# PX4FMUlite_V0_3.net
KiCad netlist of a schematic drawn in EAGLE
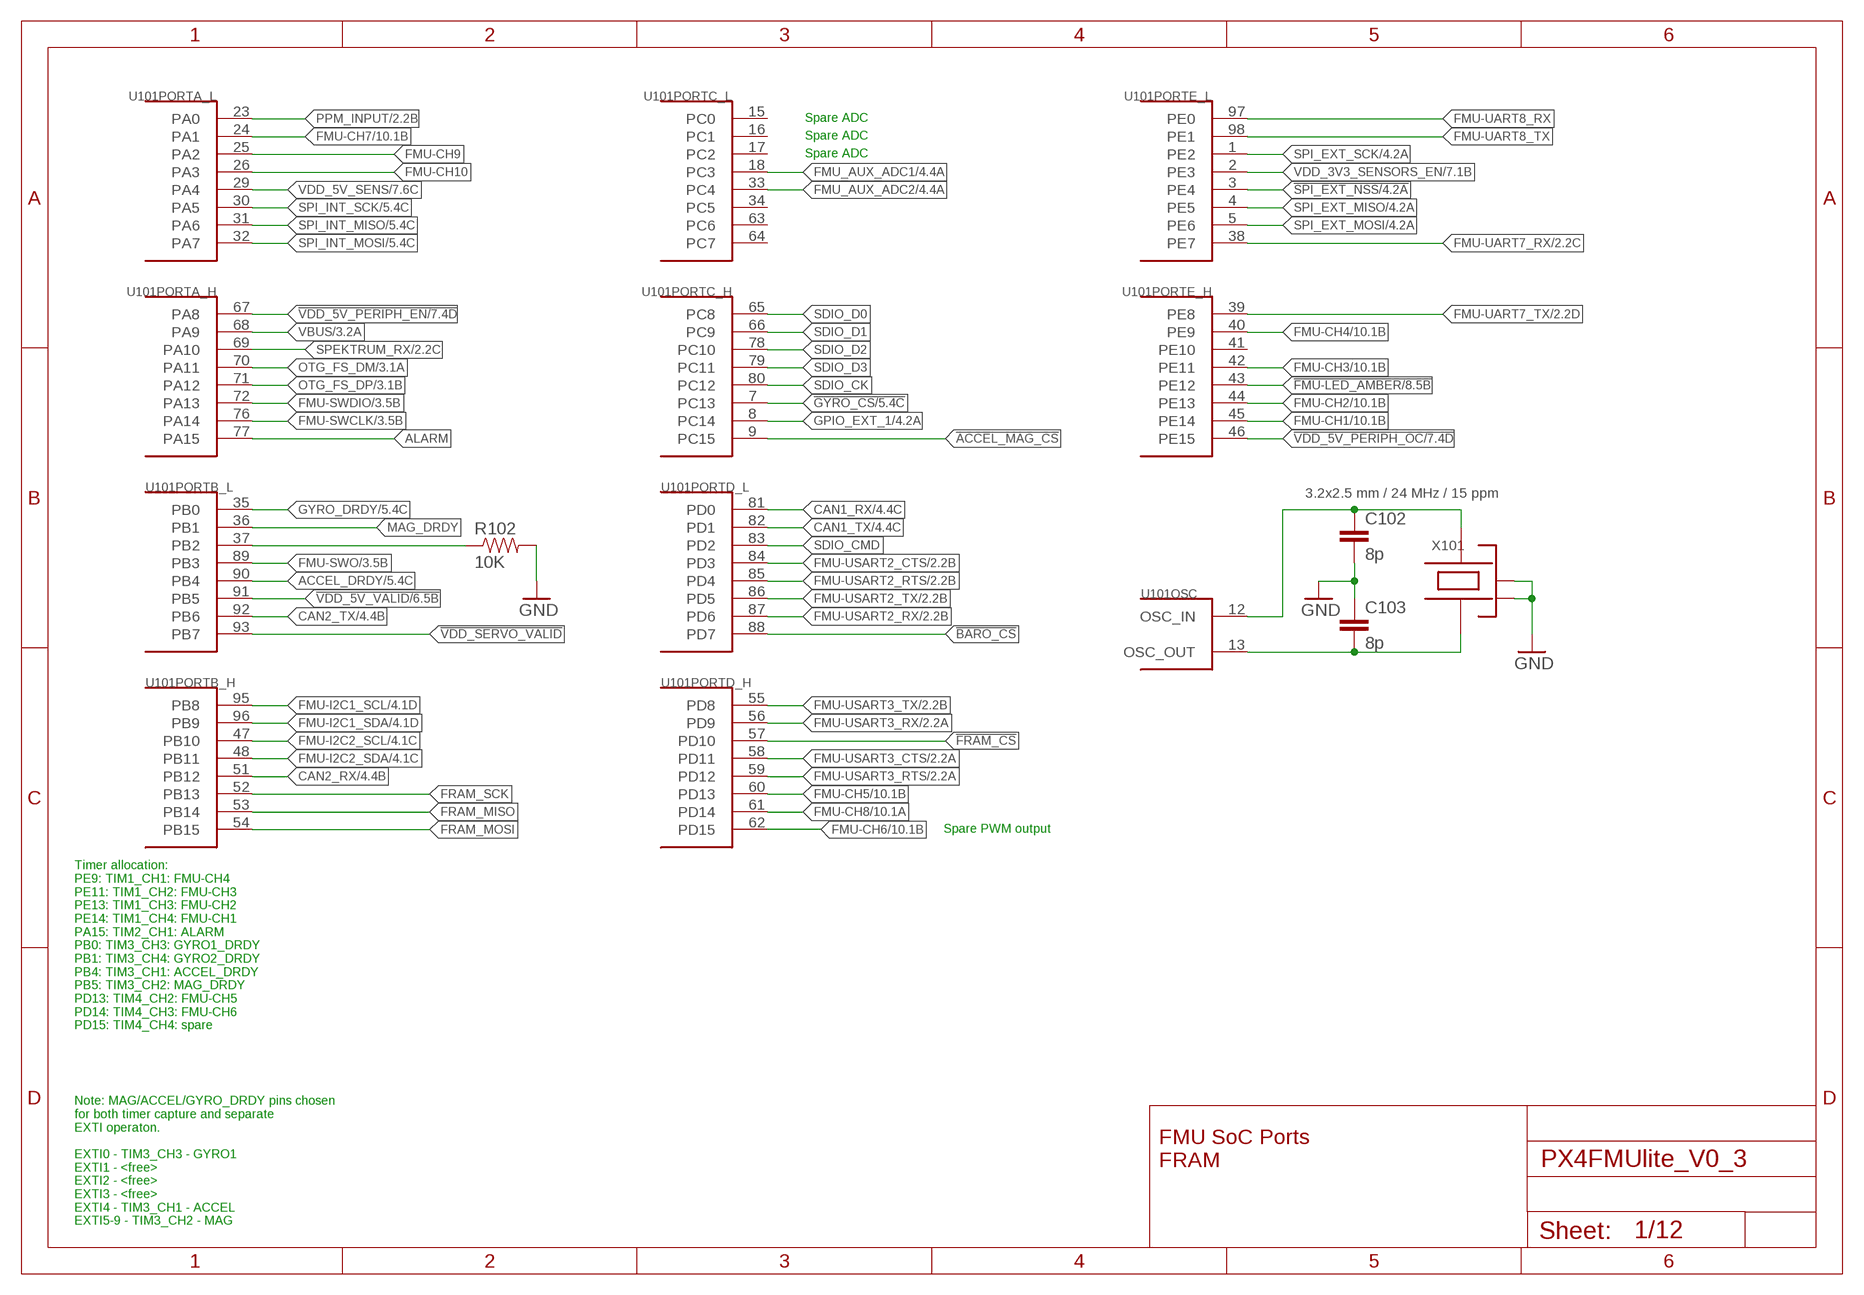
[diagram p0: schematic, sheet 1]
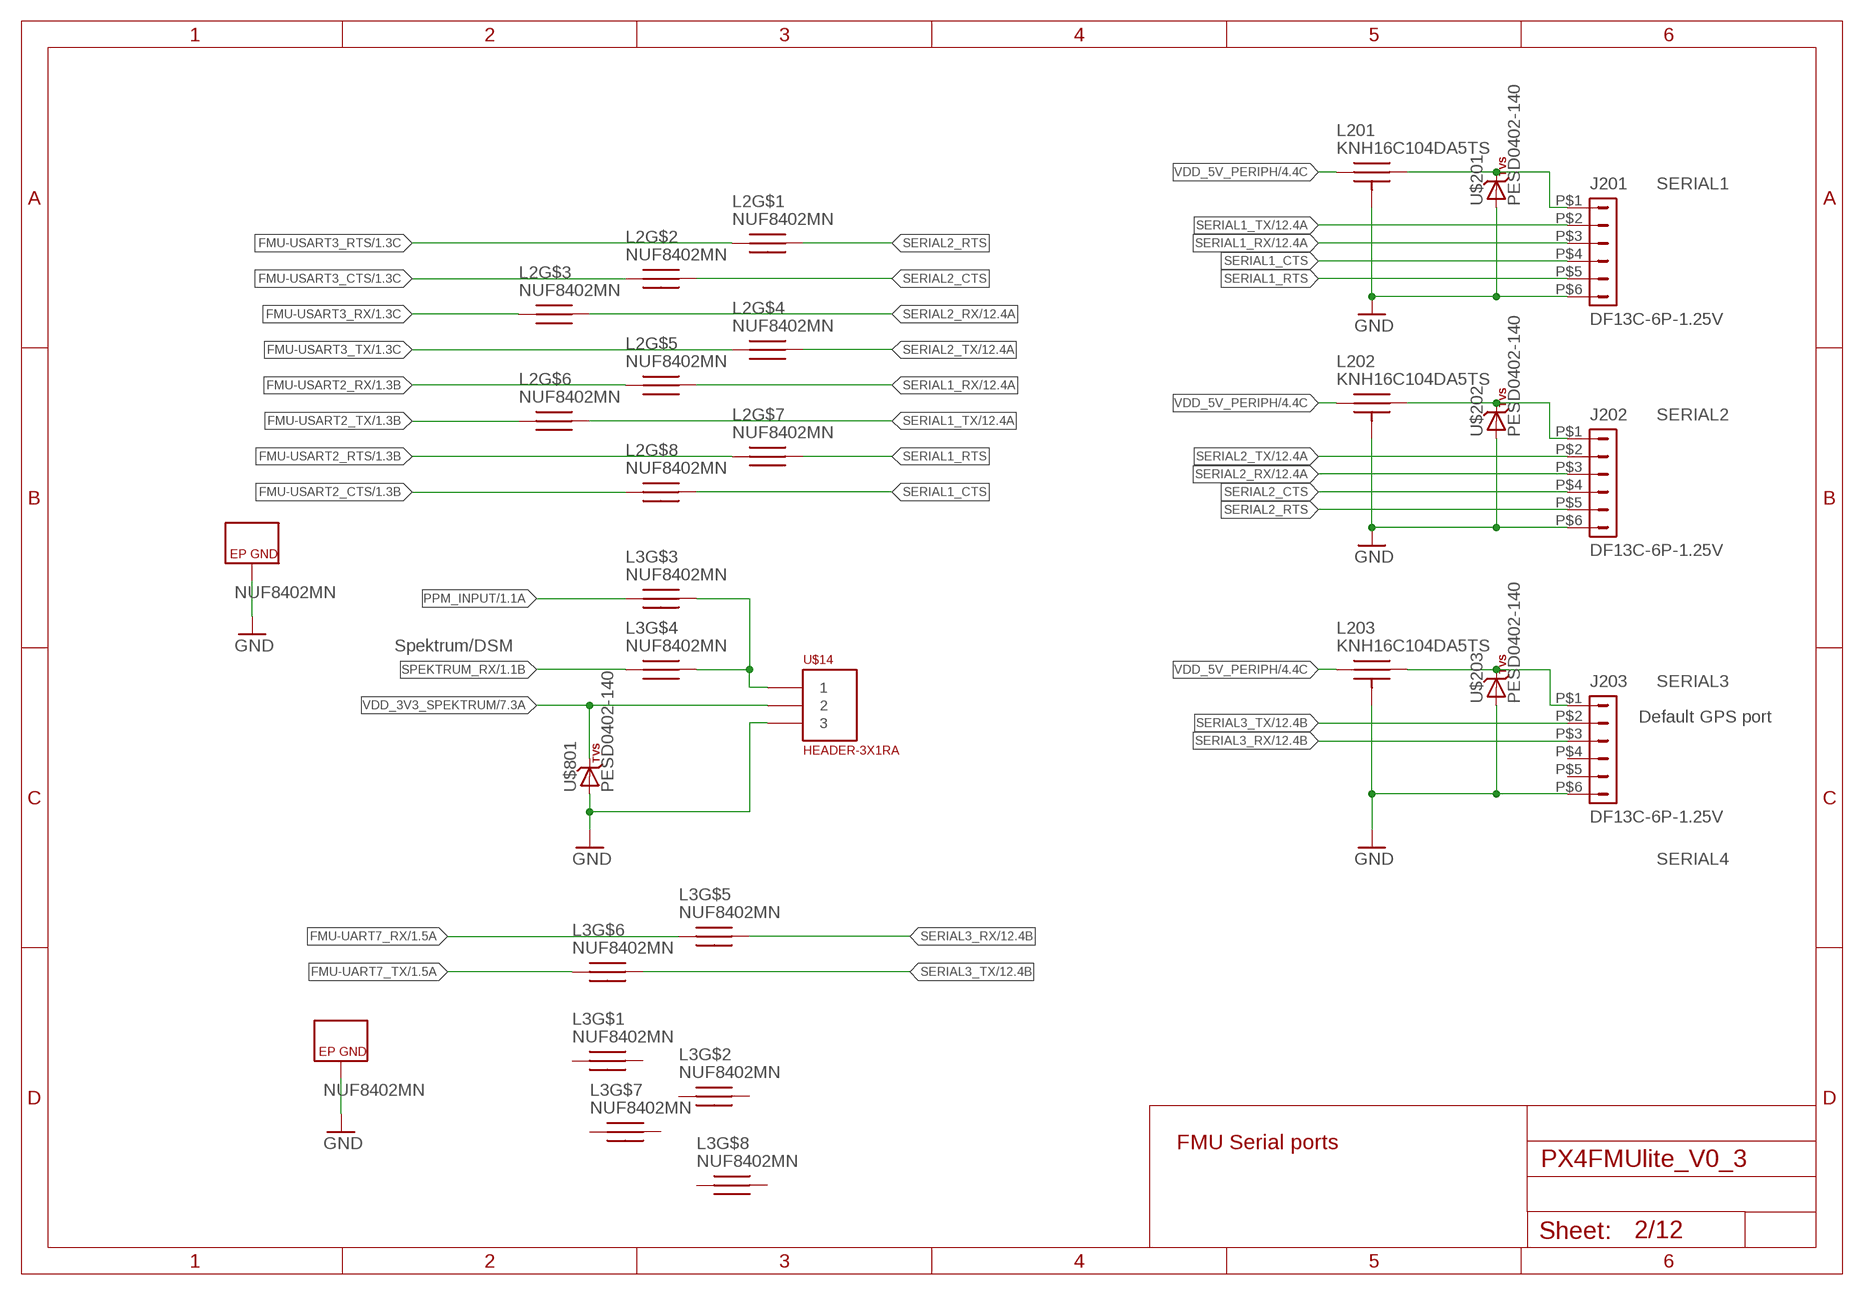
[diagram p1: schematic, sheet 2]
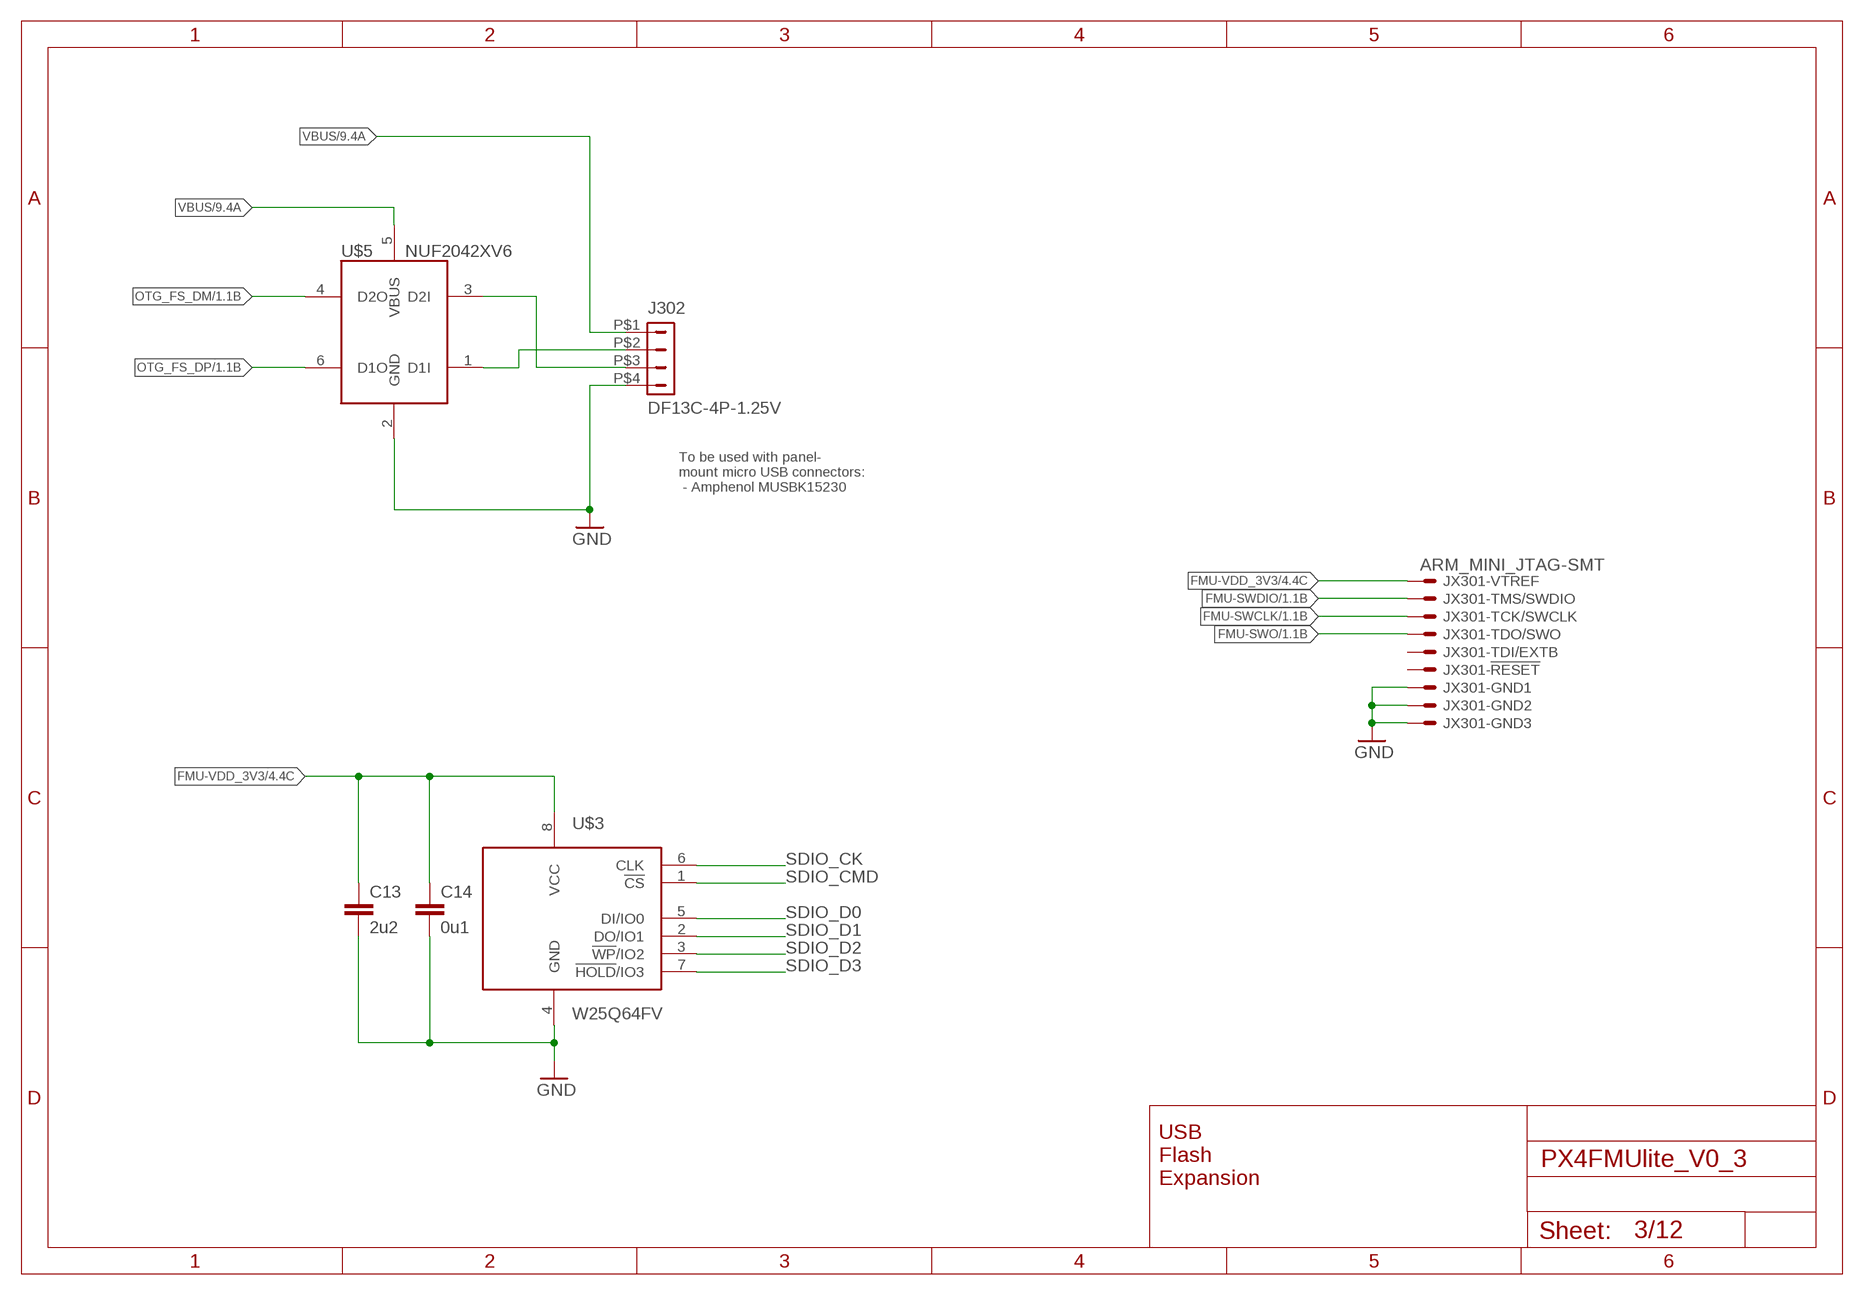
[diagram p2: schematic, sheet 3]
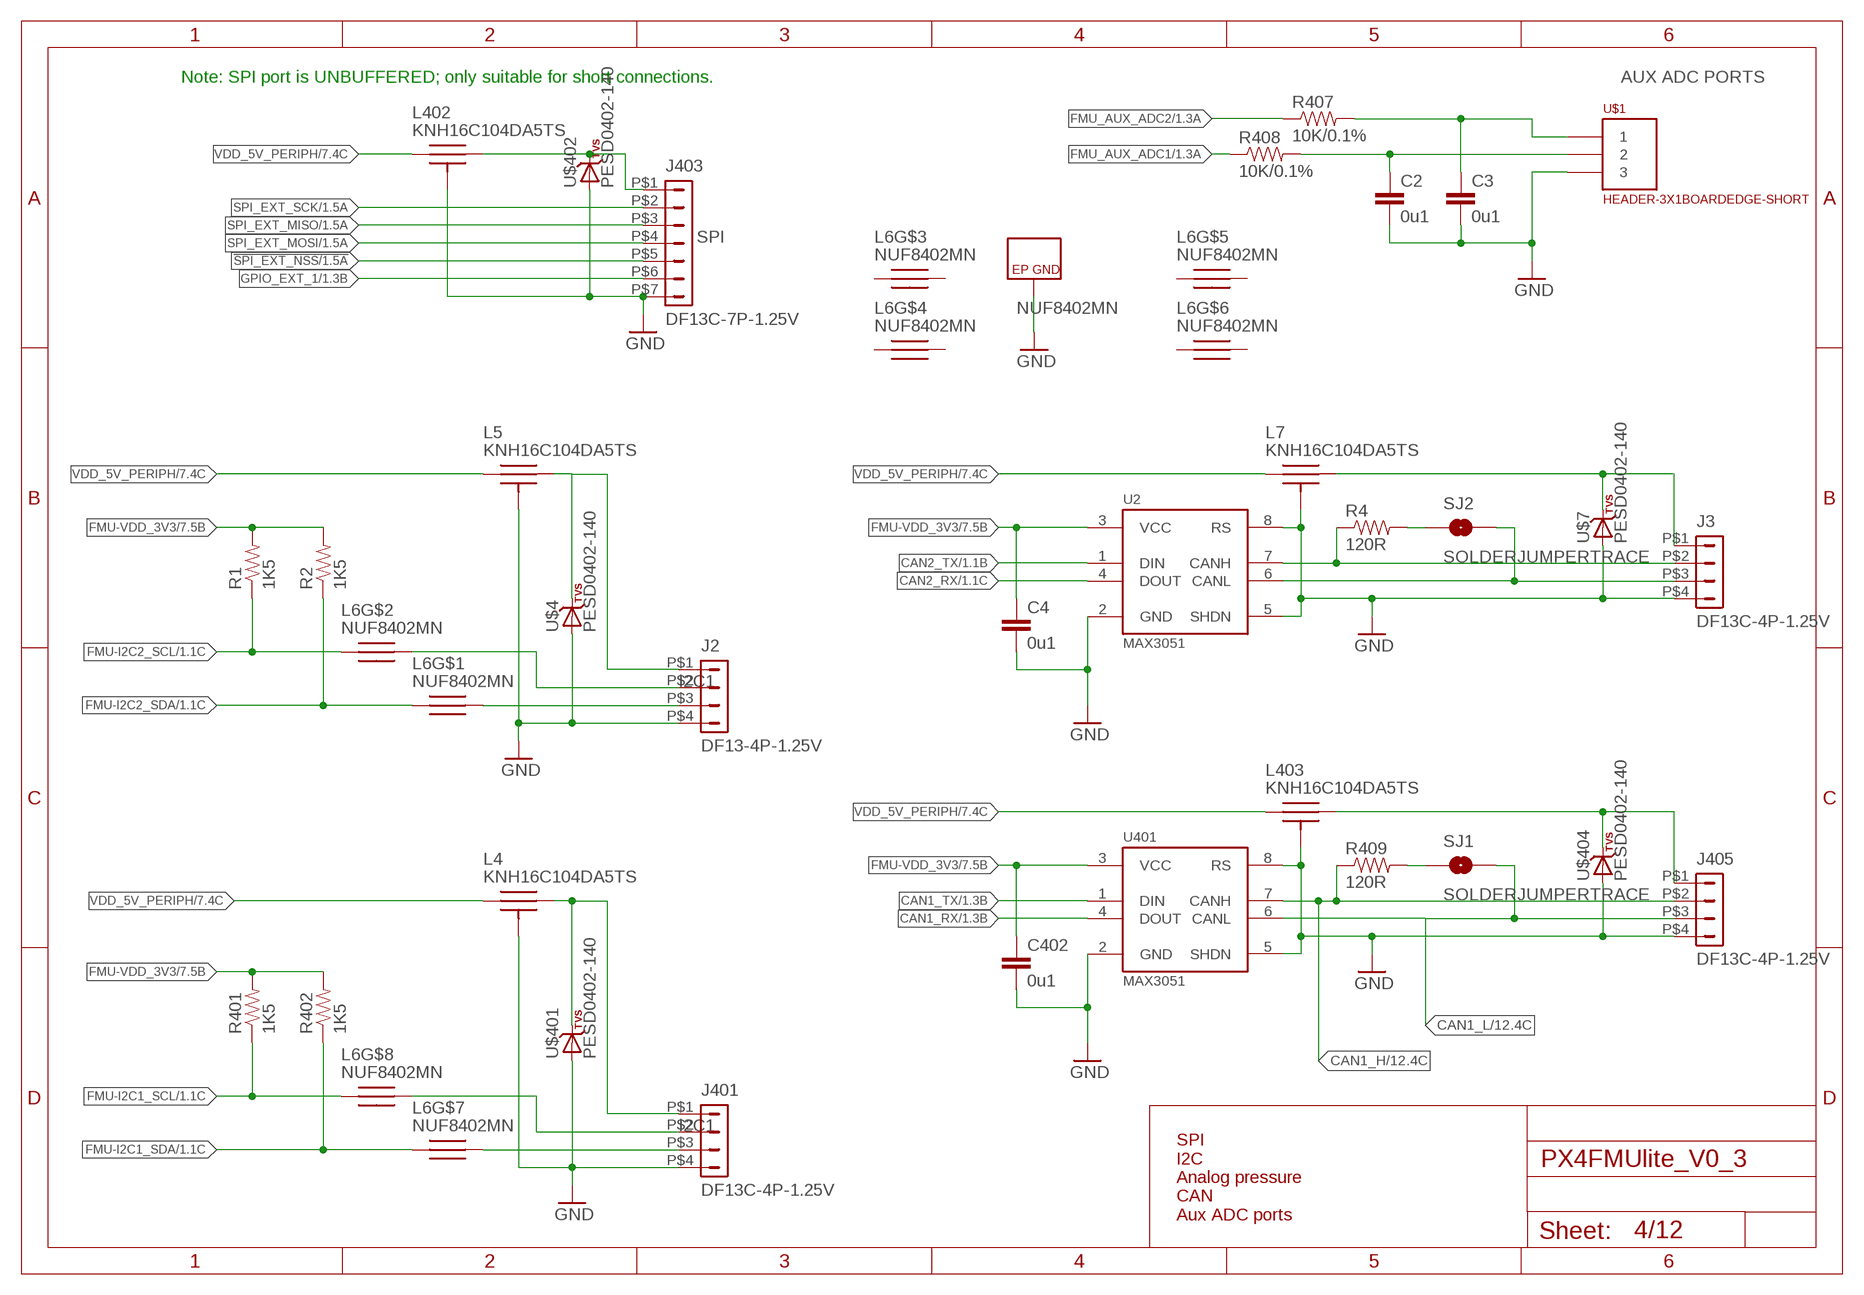
[diagram p3: schematic, sheet 4]
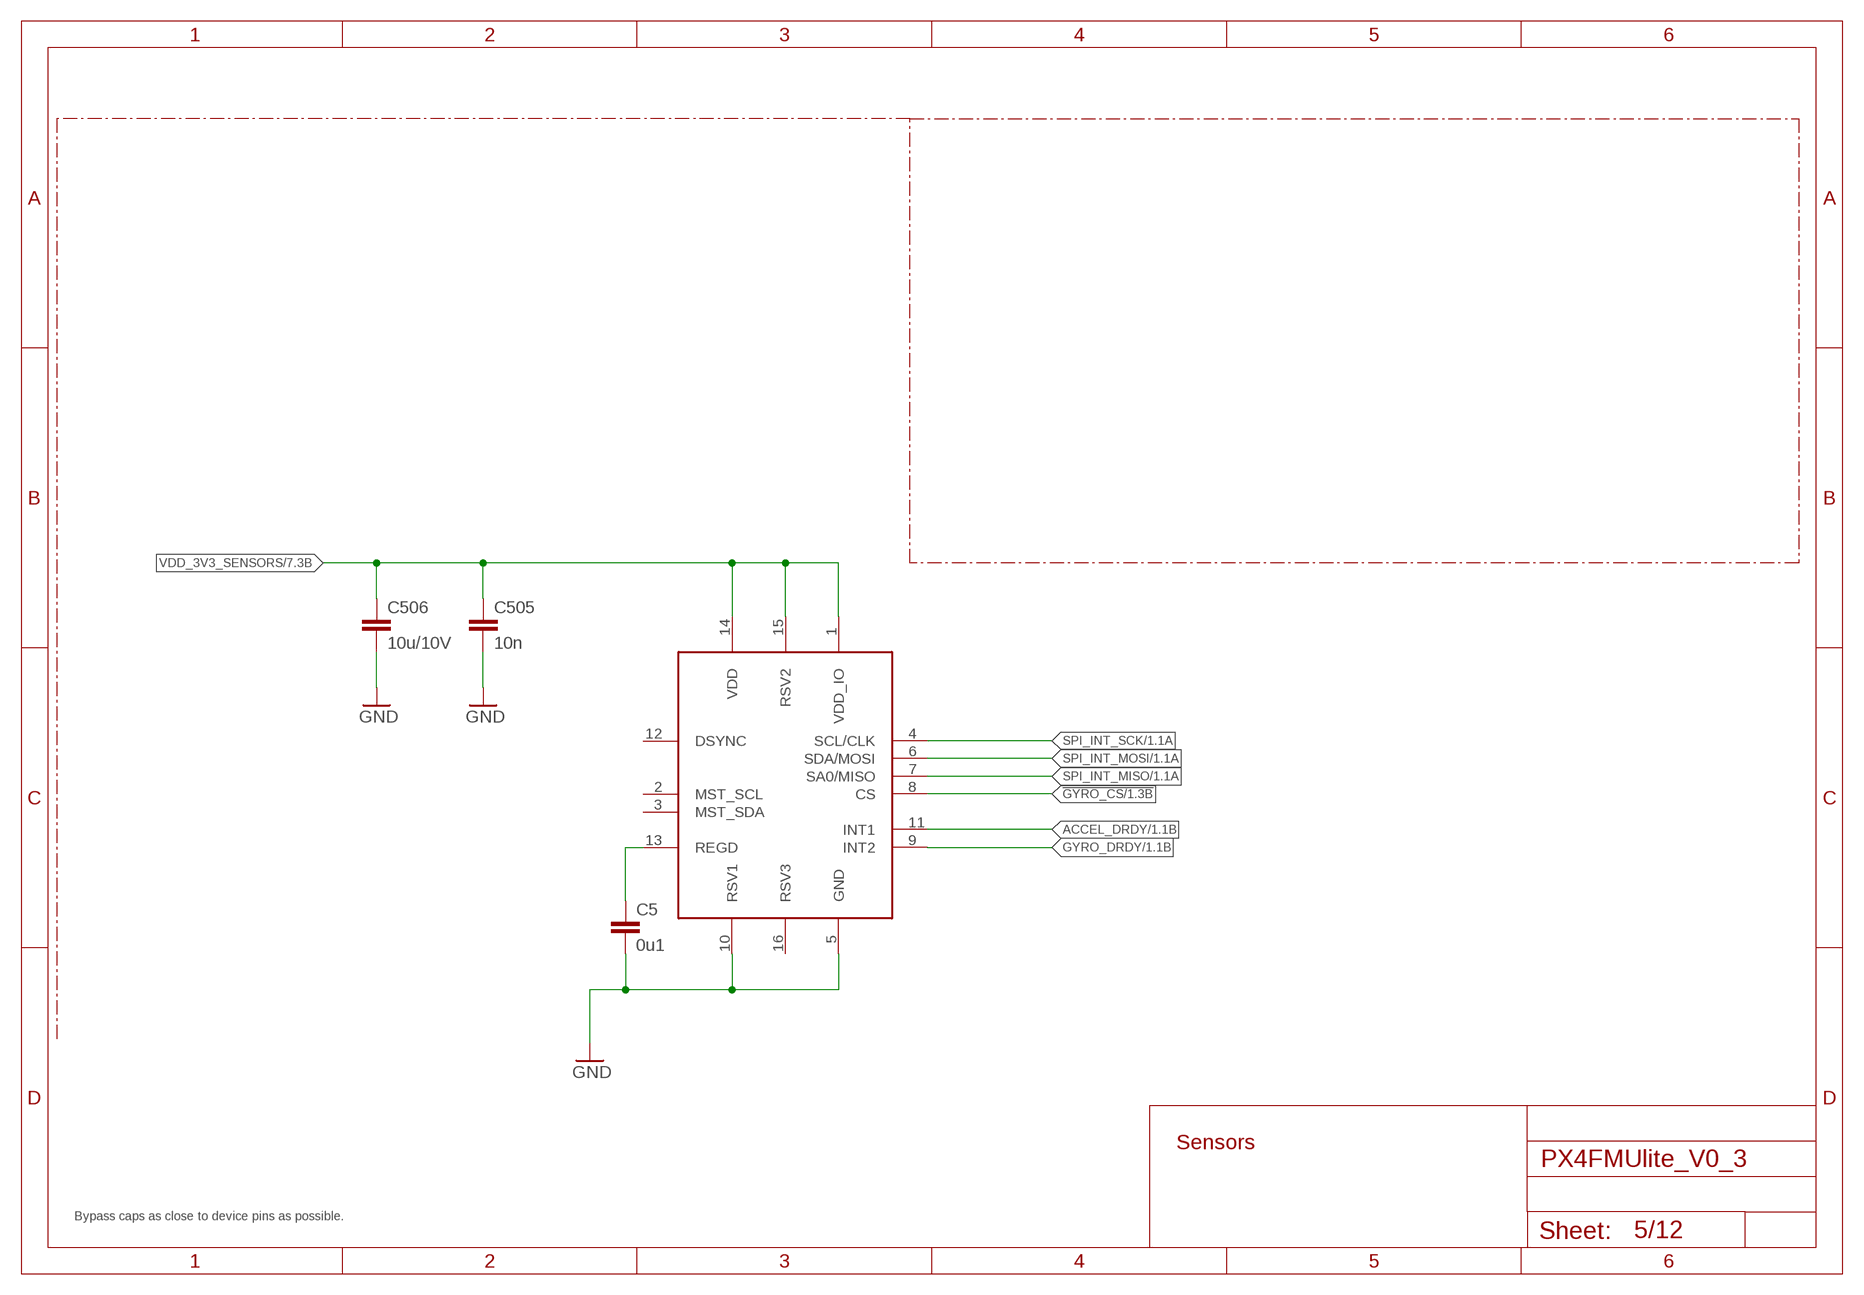
[diagram p4: schematic, sheet 5]
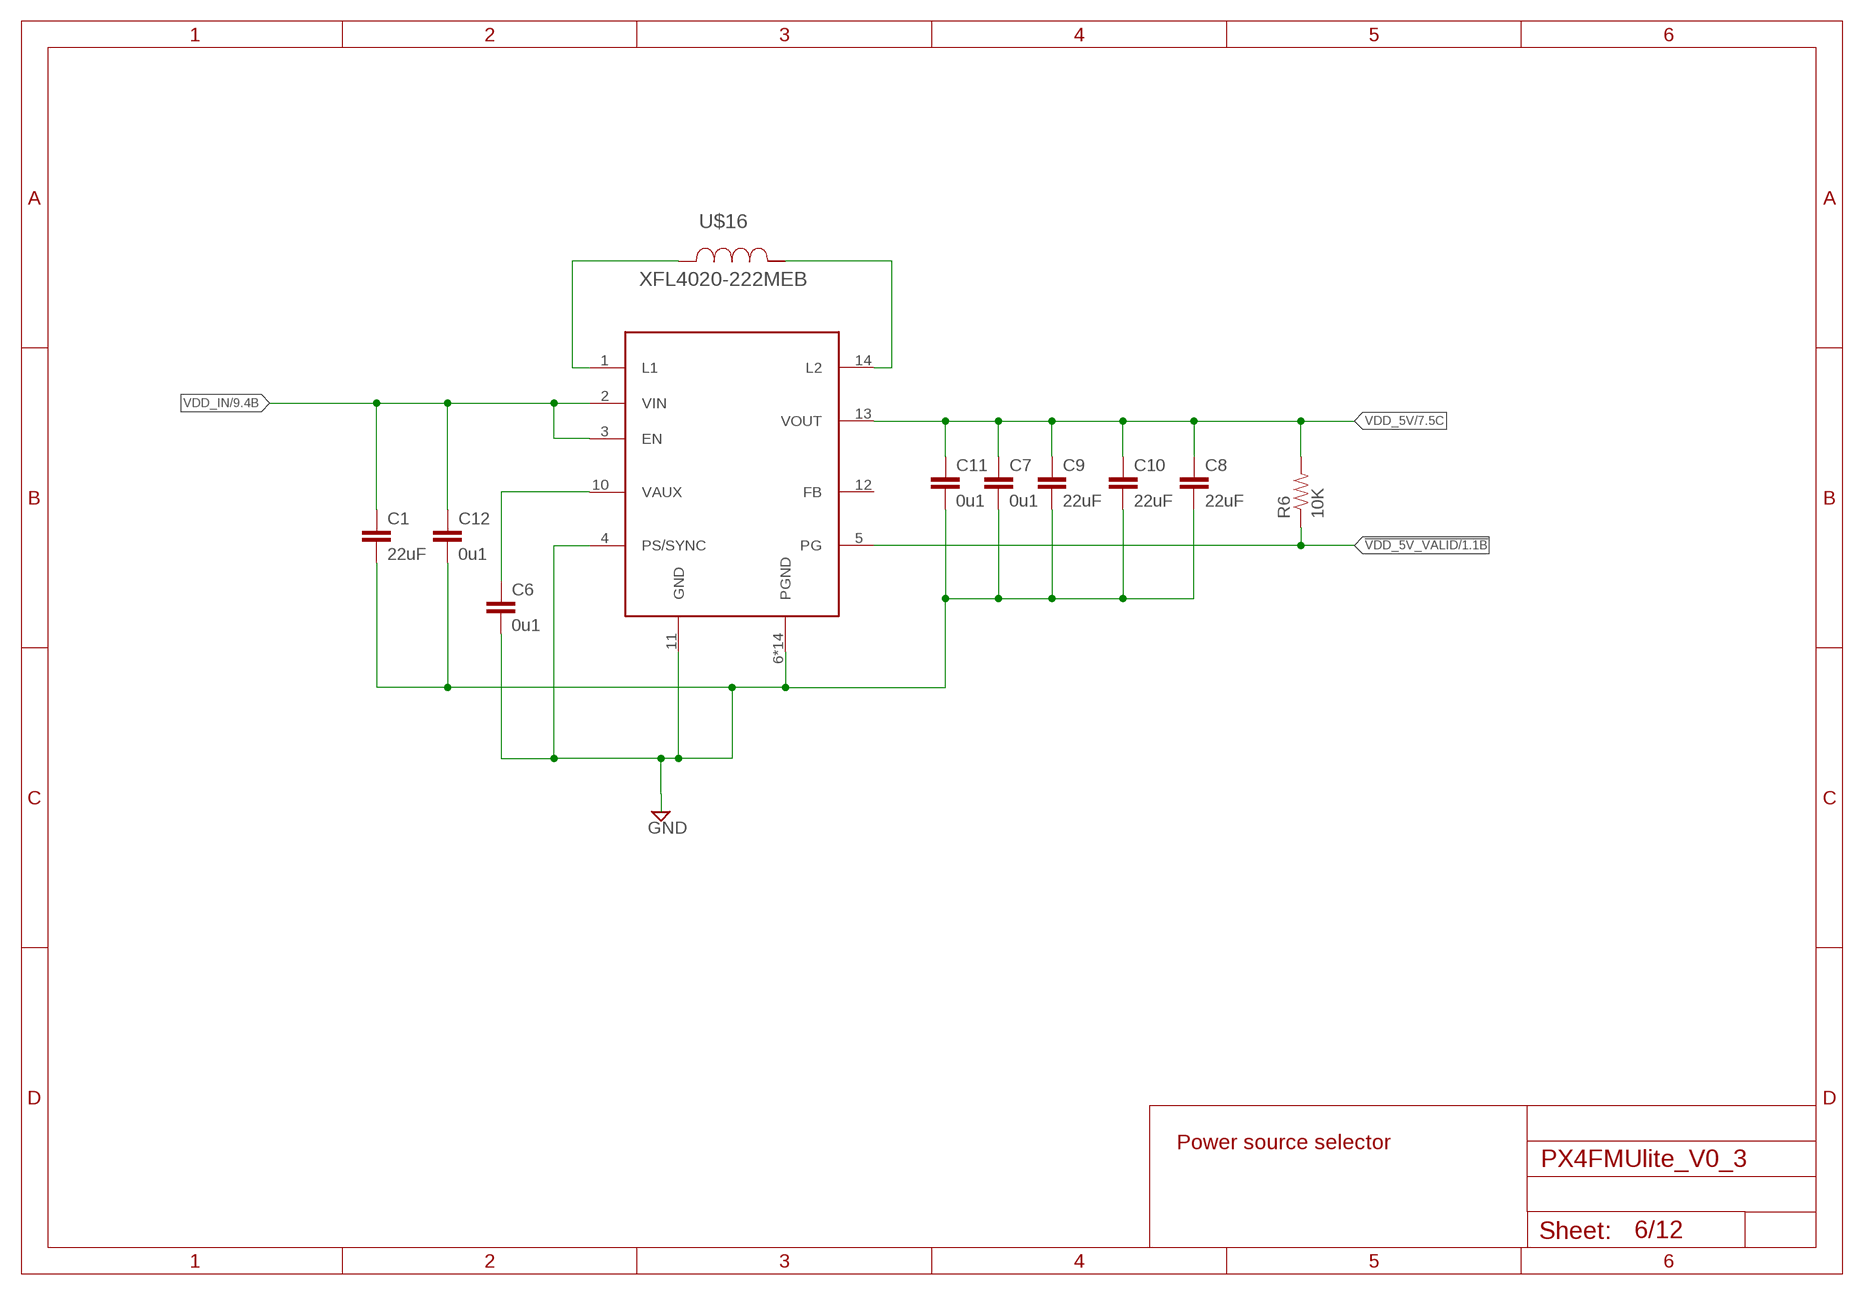
[diagram p5: schematic, sheet 6]
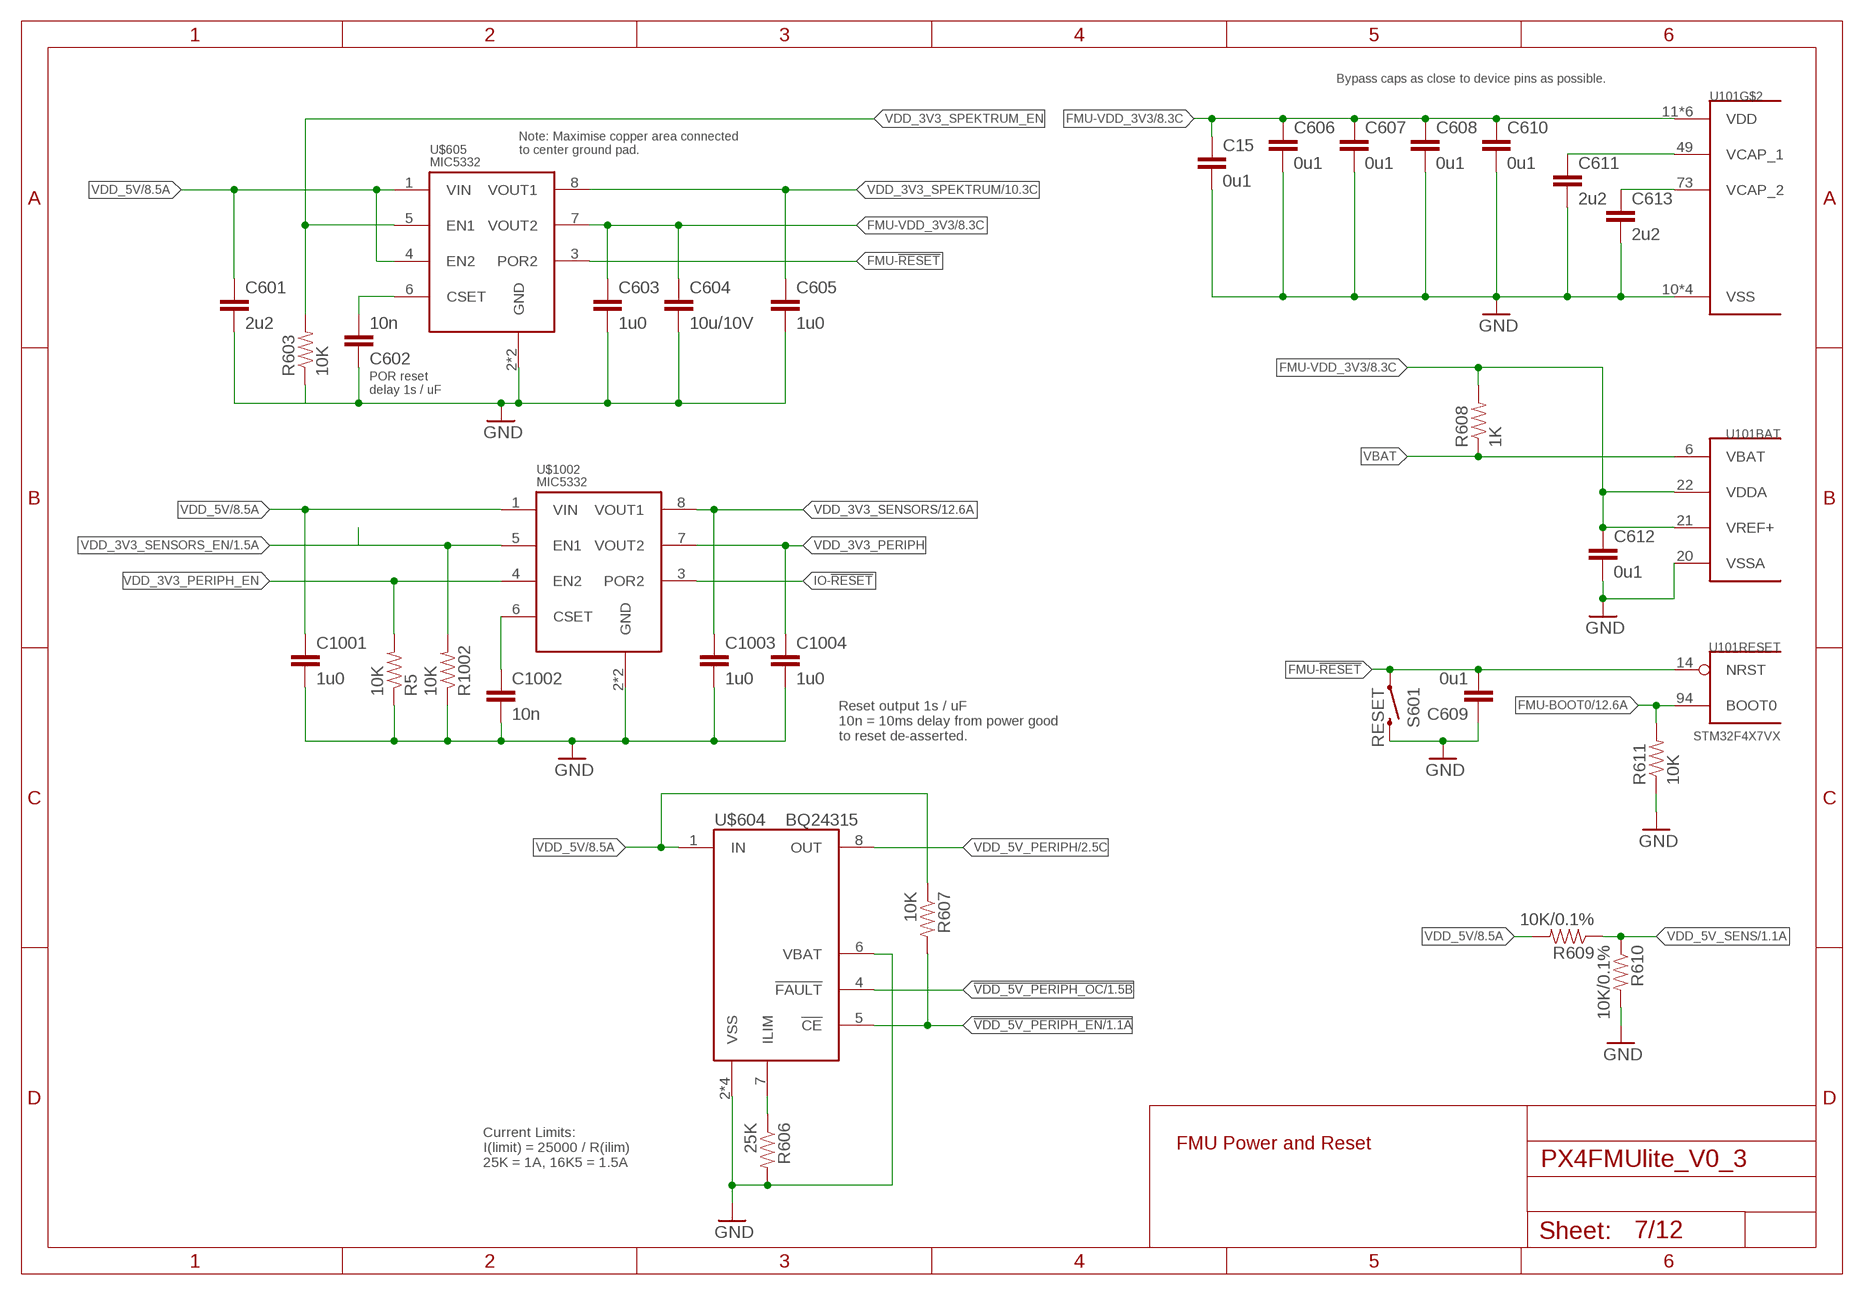
[diagram p6: schematic, sheet 7]
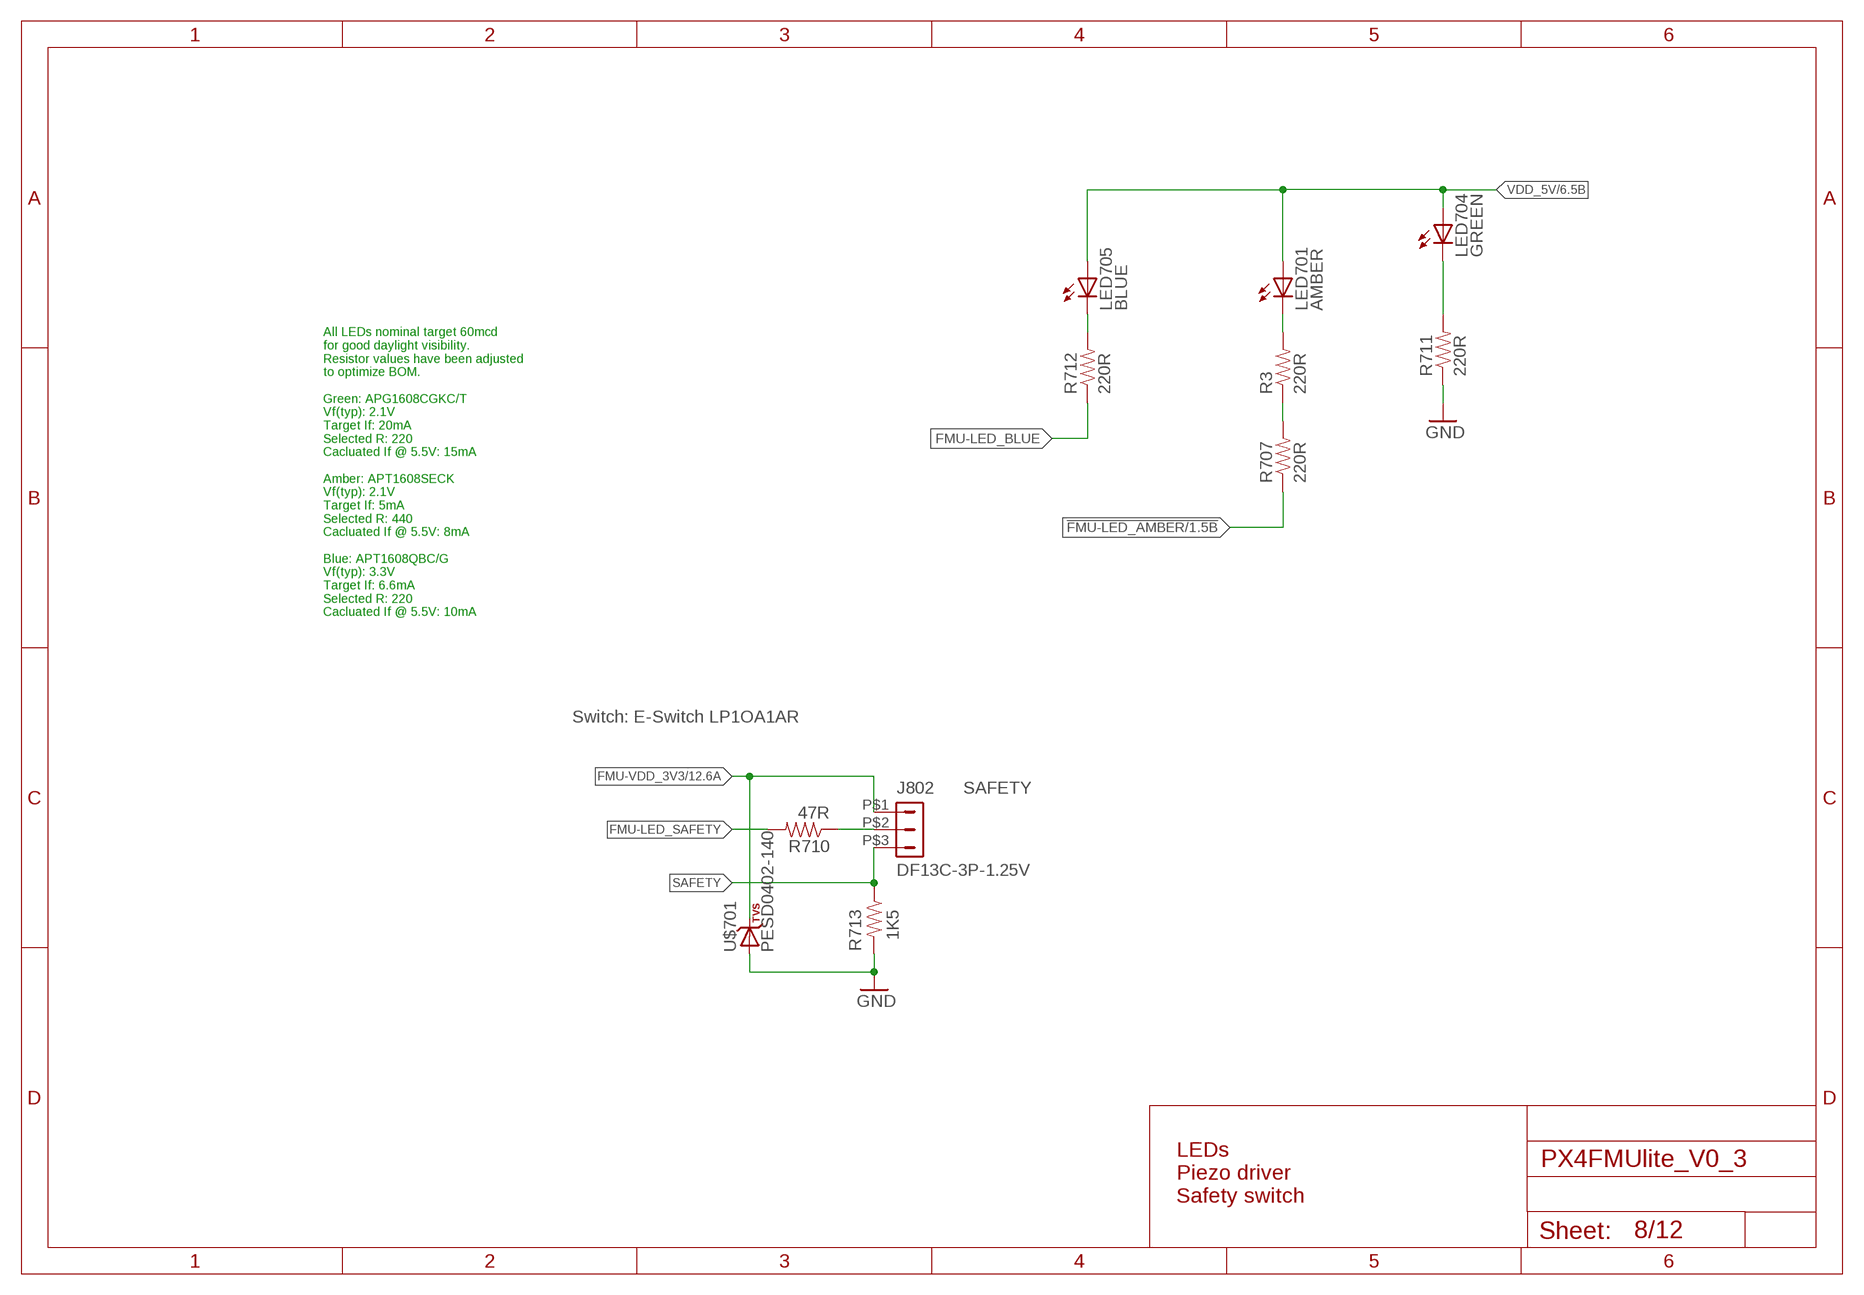
[diagram p7: schematic, sheet 8]
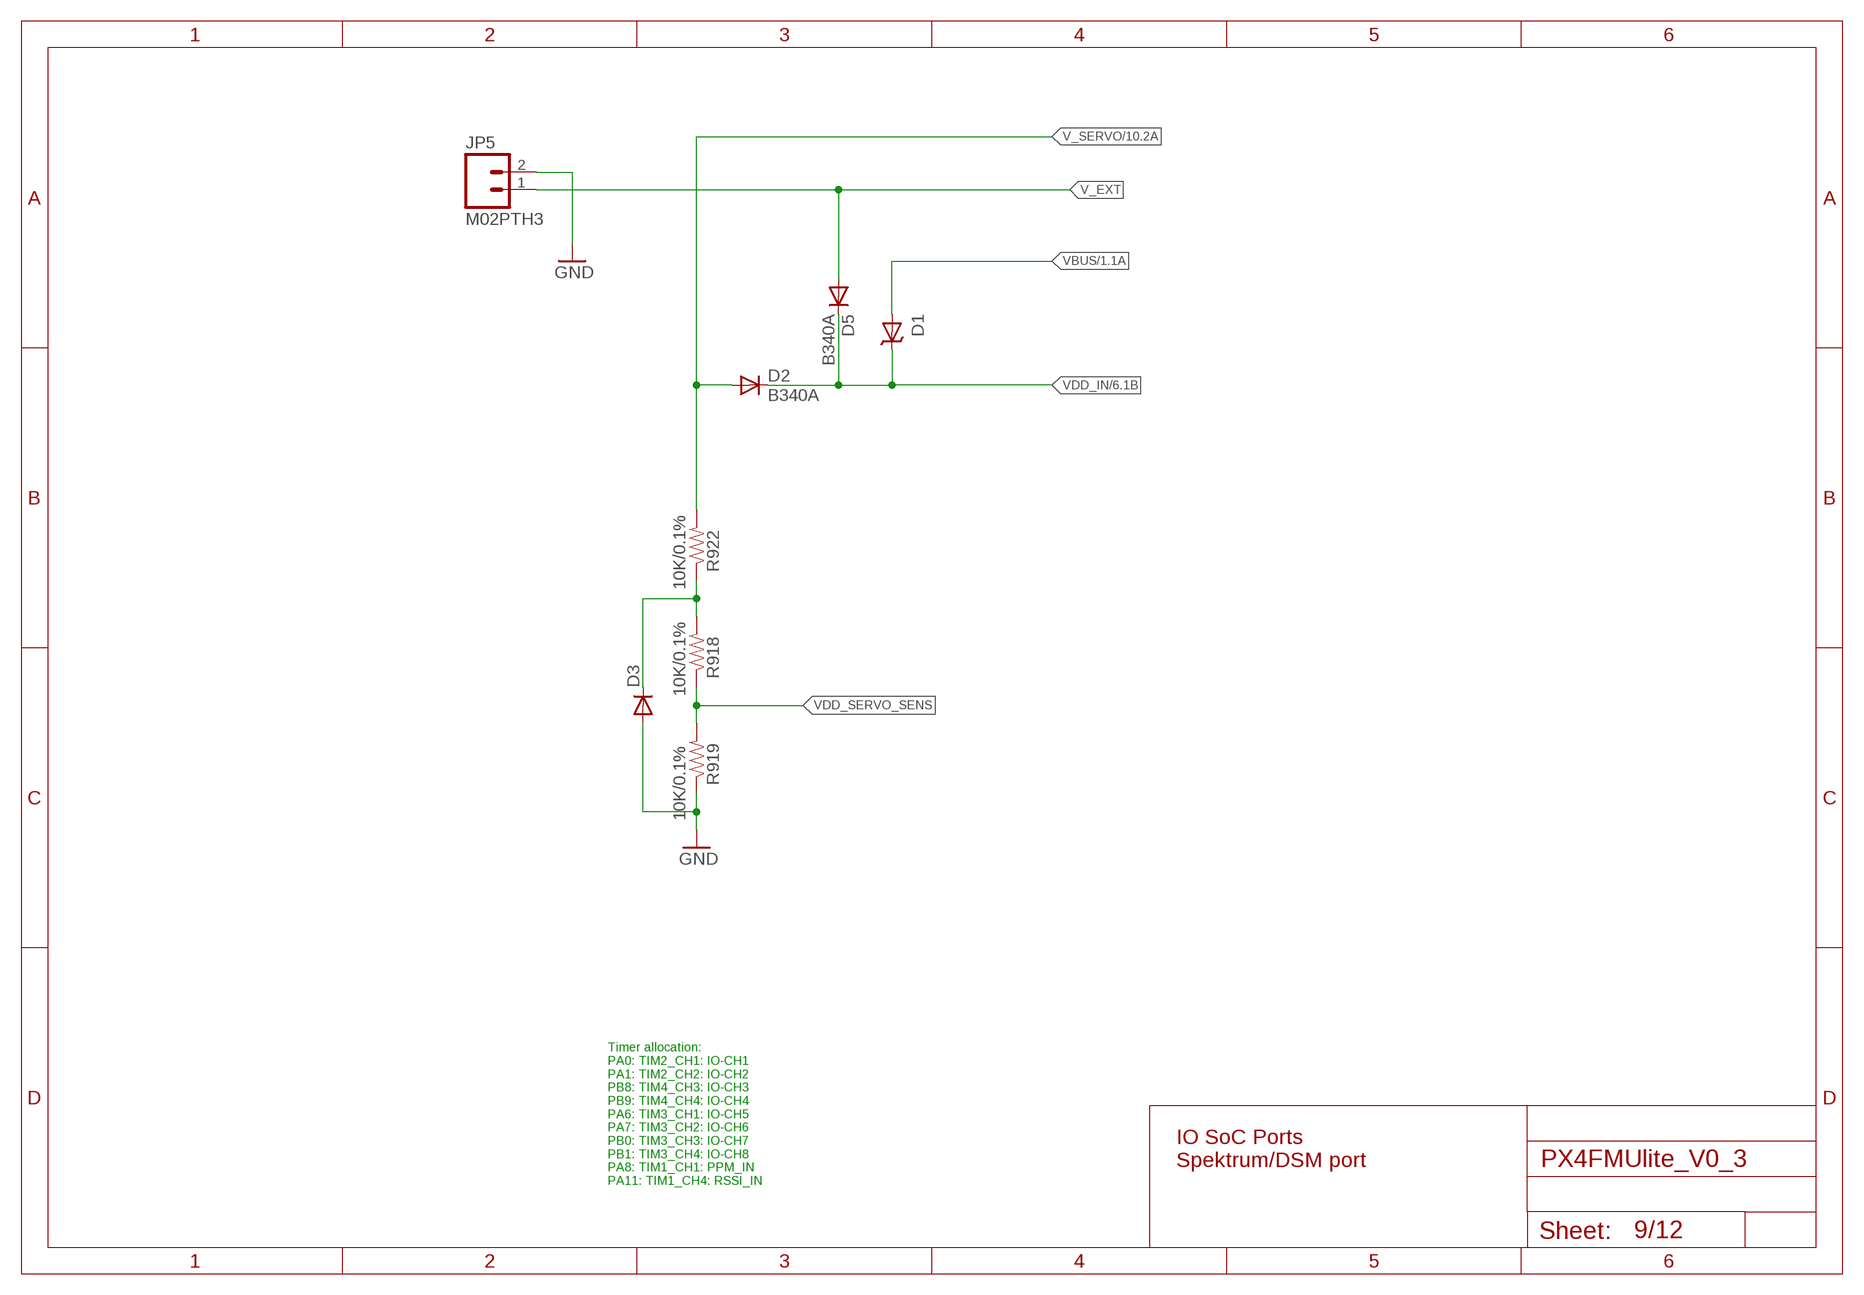
[diagram p8: schematic, sheet 9]
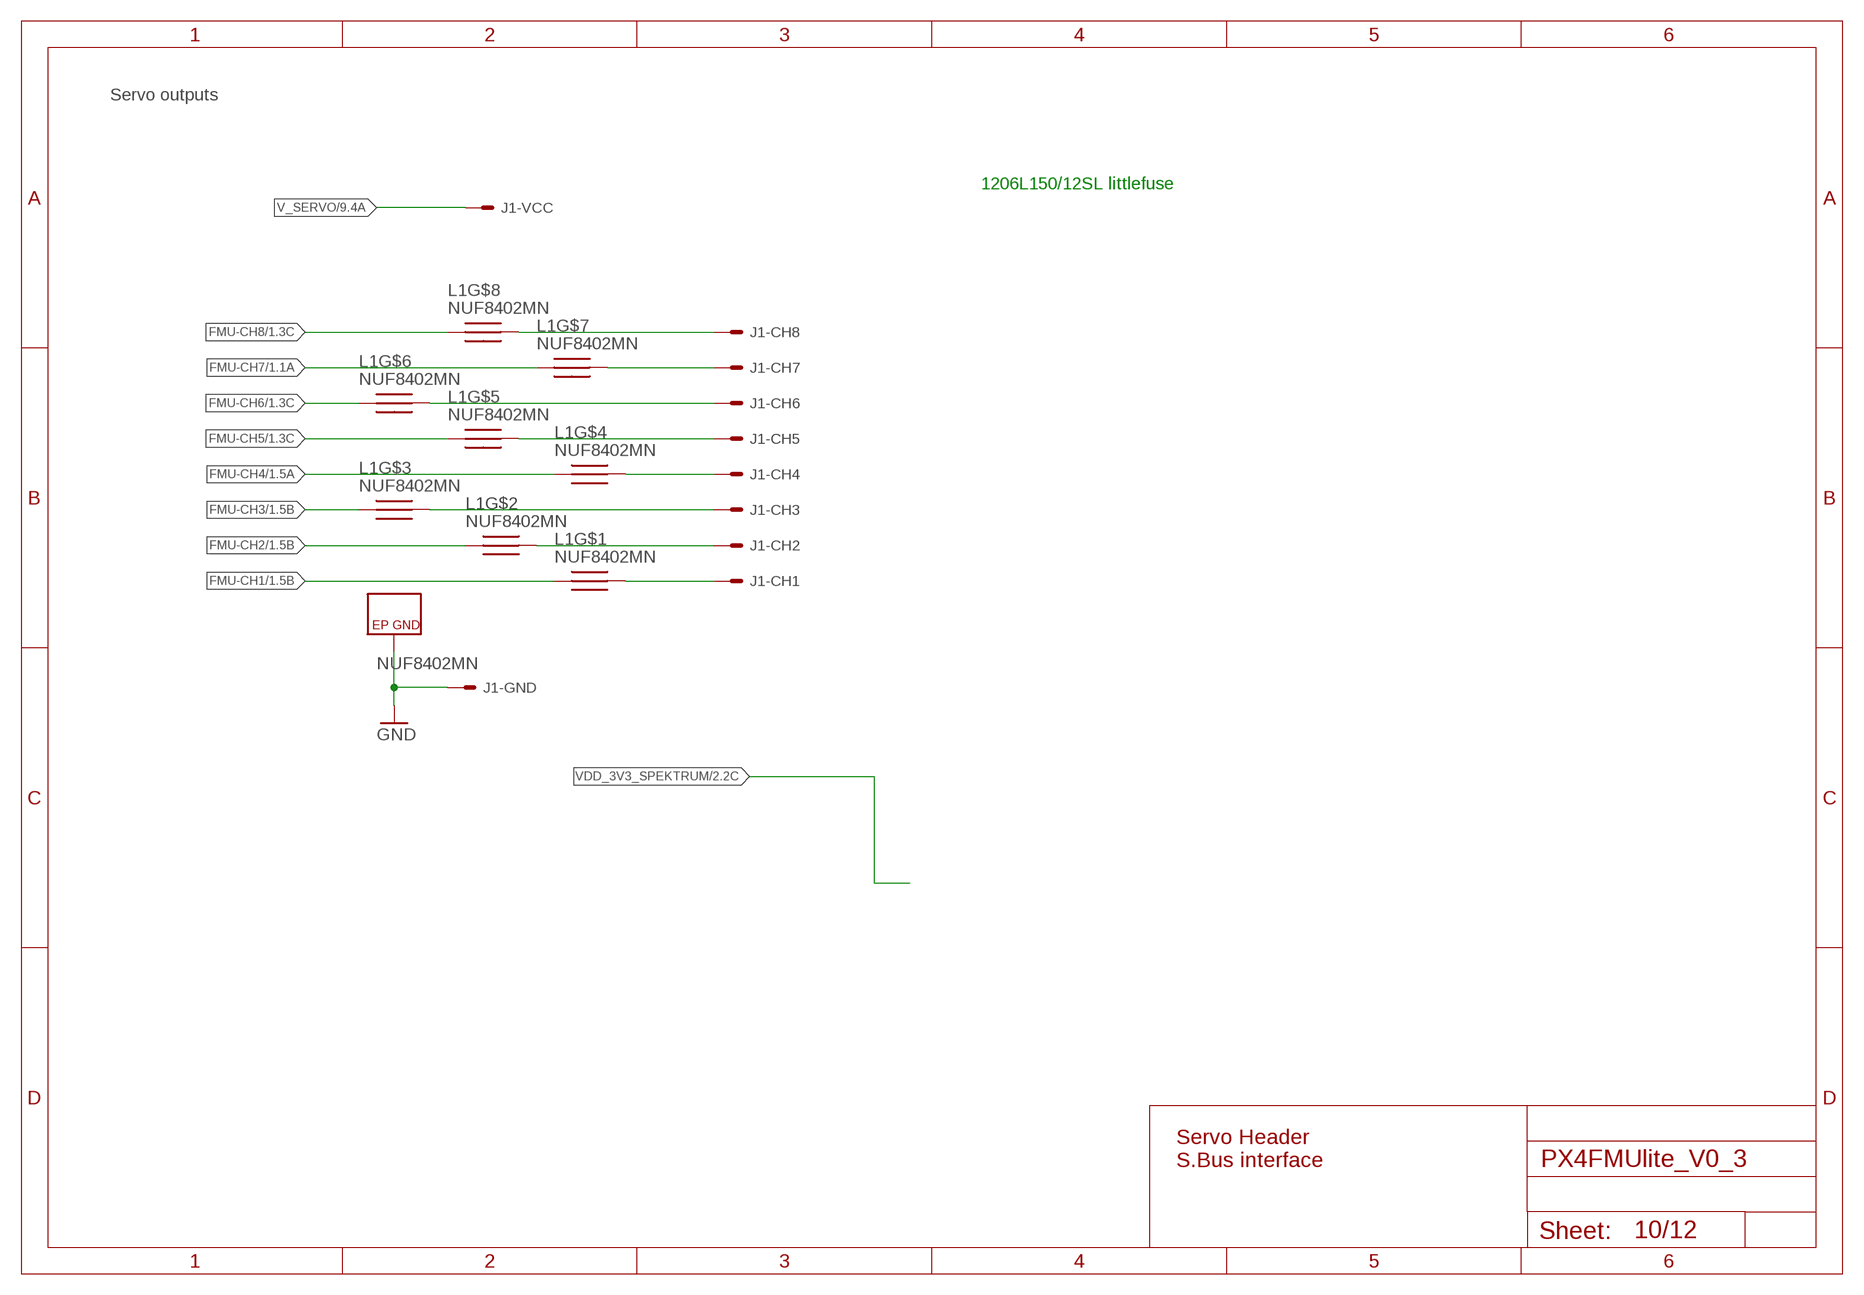
[diagram p9: schematic, sheet 10]
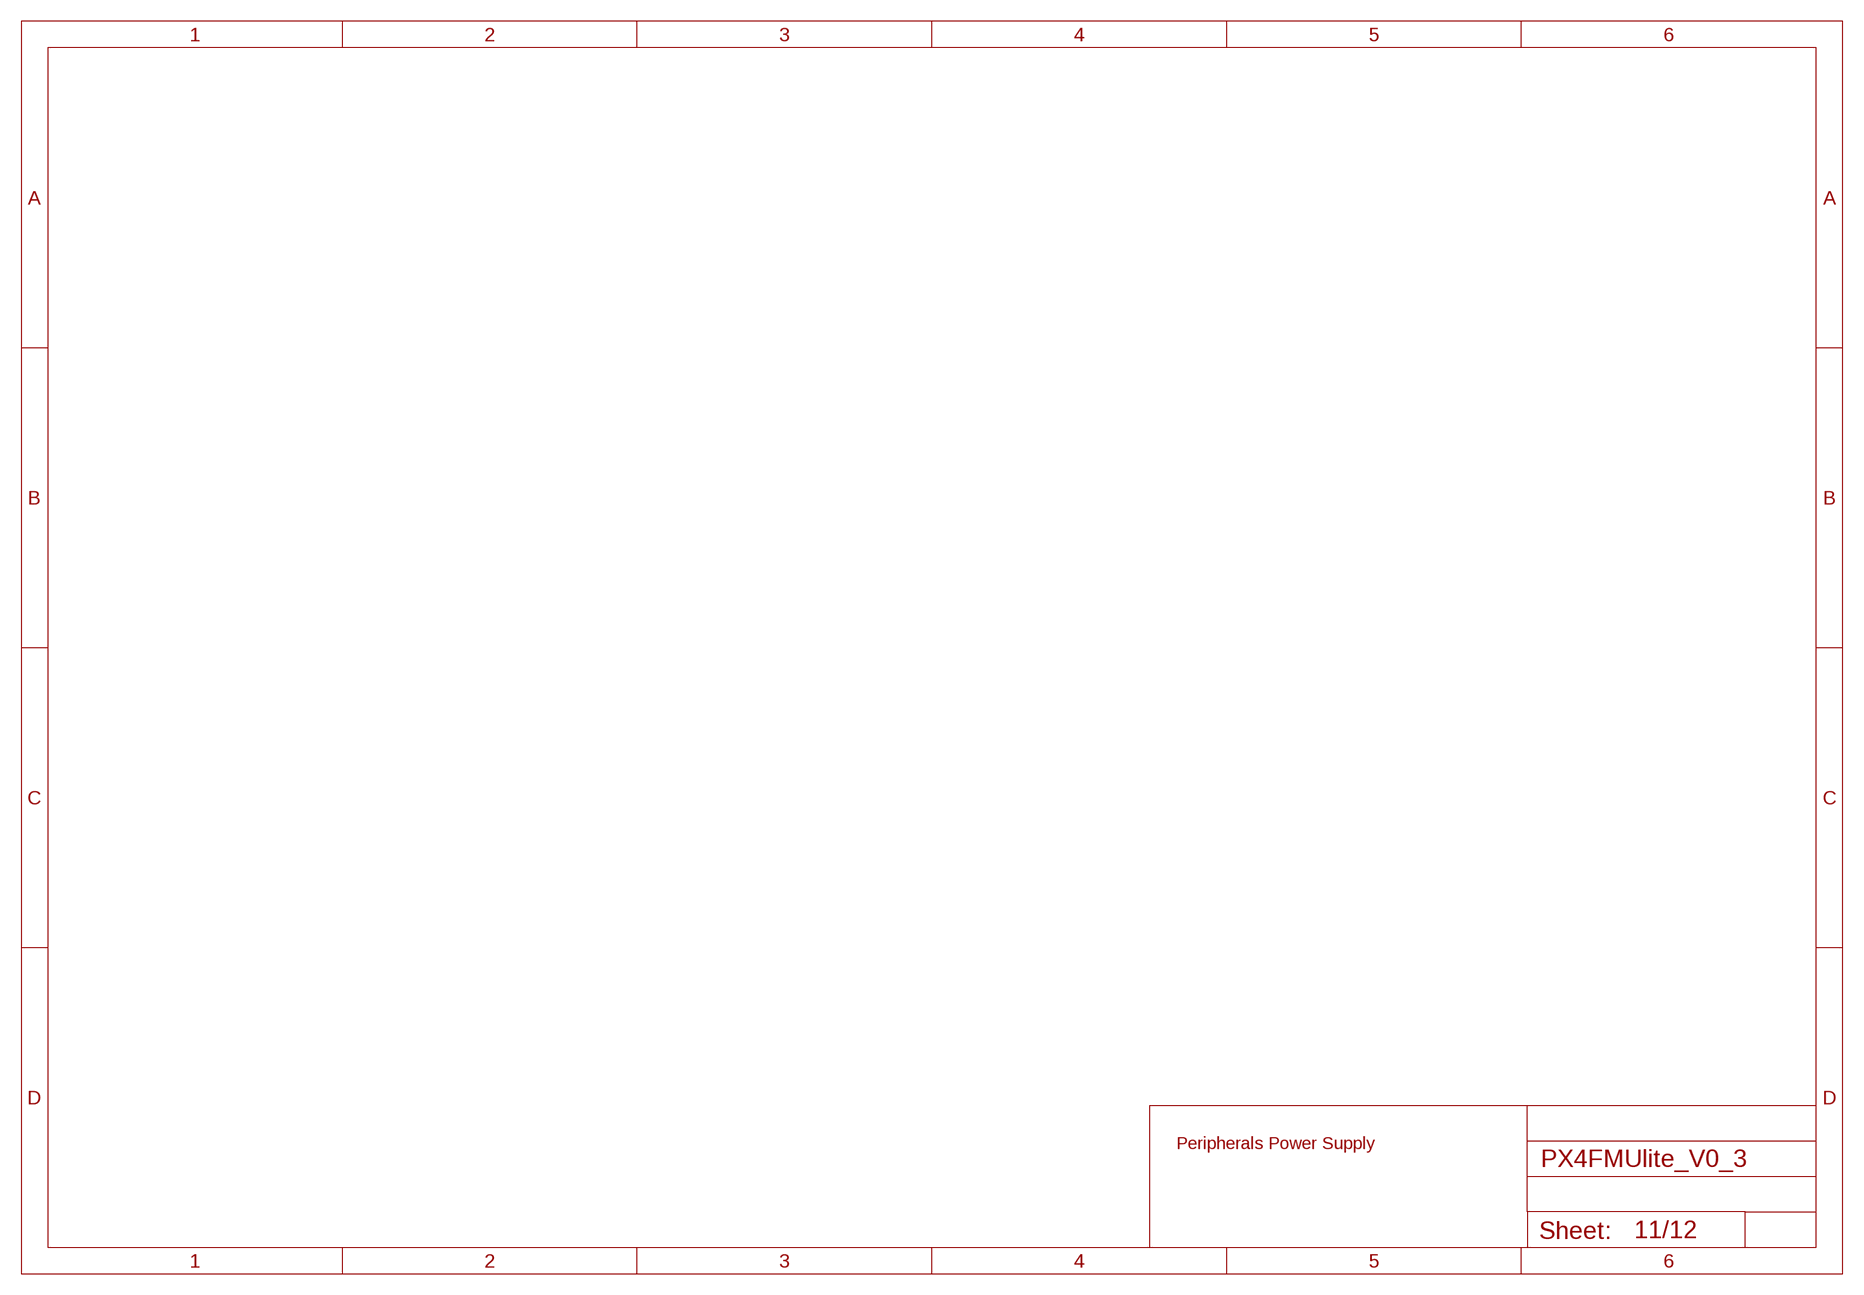
[diagram p10: schematic, sheet 11]
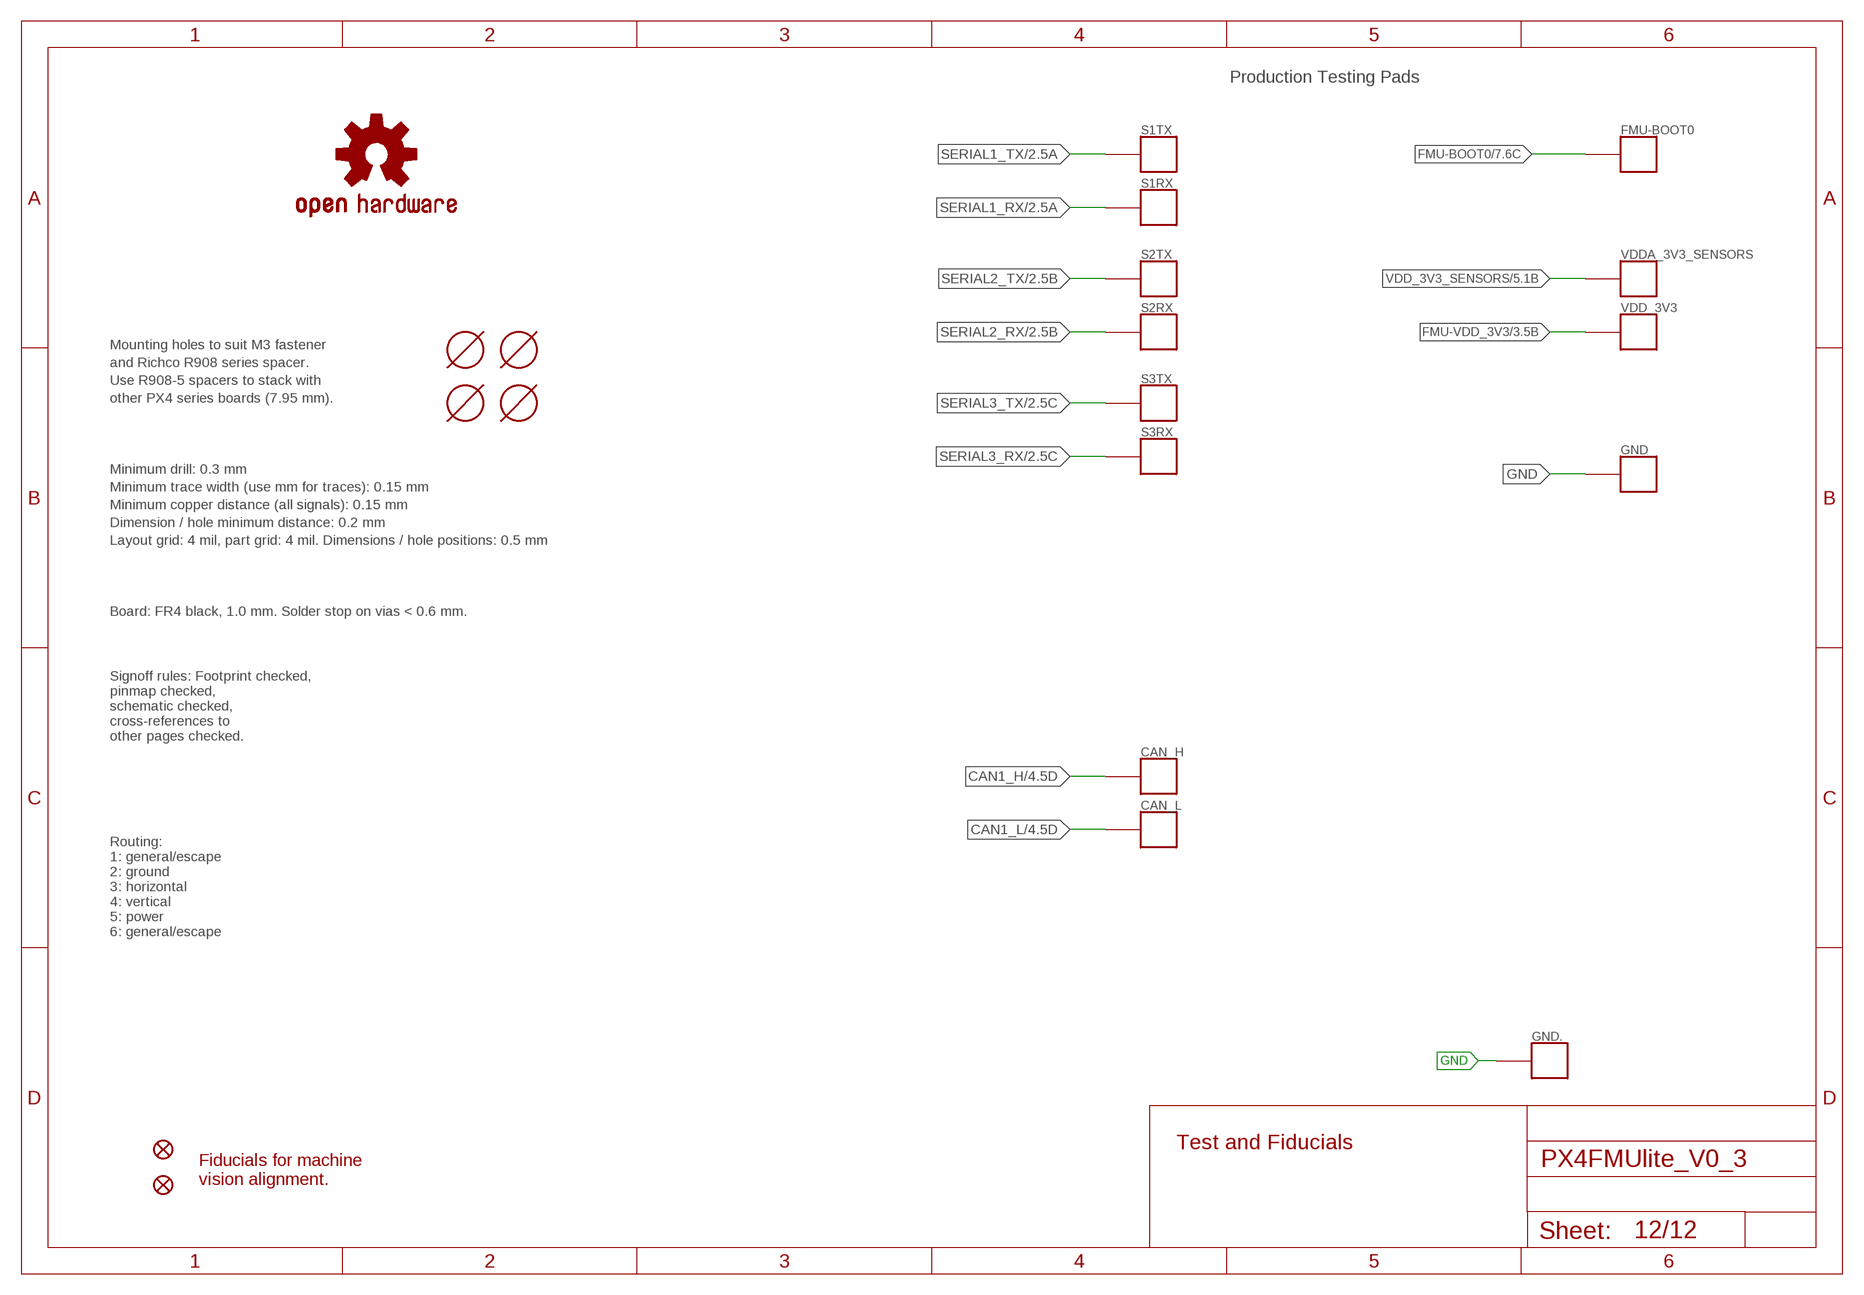
[diagram p11: schematic, sheet 12]

(export (version "E")
  (design (tool "Eeschema 10.0.6"))
  (components
    (comp (ref "J201")
      (value "DF13C-6P-1.25V")
      (footprint "eagle-import:DF13C-6P-1.25V")
      (fields (field (name "PARTNO") "DF13C-6P-1.25V(20)"))
      (libsource (lib "eagle-import") (part "DF13-6P-1.25V"))
    )
    (comp (ref "J202")
      (value "DF13C-6P-1.25V")
      (footprint "eagle-import:DF13C-6P-1.25V")
      (fields (field (name "PARTNO") "DF13C-6P-1.25V(20)"))
      (libsource (lib "eagle-import") (part "DF13-6P-1.25V"))
    )
    (comp (ref "J203")
      (value "DF13C-6P-1.25V")
      (footprint "eagle-import:DF13C-6P-1.25V")
      (fields (field (name "PARTNO") "DF13C-6P-1.25V(20)"))
      (libsource (lib "eagle-import") (part "DF13-6P-1.25V"))
    )
    (comp (ref "L2")
      (value "NUF8402MN")
      (footprint "eagle-import:DFN16-THIN")
      (libsource (lib "eagle-import") (part "NUF8402MN"))
    )
    (comp (ref "L3")
      (value "NUF8402MN")
      (footprint "eagle-import:DFN16-THIN")
      (libsource (lib "eagle-import") (part "NUF8402MN"))
    )
    (comp (ref "L201")
      (value "KNH16C104DA5TS")
      (footprint "eagle-import:KYOCERA-KNH16-DA")
      (libsource (lib "eagle-import") (part "KNH16C104DA5TS"))
    )
    (comp (ref "L202")
      (value "KNH16C104DA5TS")
      (footprint "eagle-import:KYOCERA-KNH16-DA")
      (libsource (lib "eagle-import") (part "KNH16C104DA5TS"))
    )
    (comp (ref "L203")
      (value "KNH16C104DA5TS")
      (footprint "eagle-import:KYOCERA-KNH16-DA")
      (libsource (lib "eagle-import") (part "KNH16C104DA5TS"))
    )
    (comp (ref "U$14")
      (value "HEADER-3X1RA")
      (footprint "eagle-import:3X1RA")
      (libsource (lib "eagle-import") (part "HEADER-3X1RA"))
    )
    (comp (ref "U$201")
      (value "PESD0402-140")
      (footprint "eagle-import:0402-TVS")
      (libsource (lib "eagle-import") (part "DIODE-TVS"))
    )
    (comp (ref "U$202")
      (value "PESD0402-140")
      (footprint "eagle-import:0402-TVS")
      (libsource (lib "eagle-import") (part "DIODE-TVS"))
    )
    (comp (ref "U$203")
      (value "PESD0402-140")
      (footprint "eagle-import:0402-TVS")
      (libsource (lib "eagle-import") (part "DIODE-TVS"))
    )
    (comp (ref "U$801")
      (value "PESD0402-140")
      (footprint "eagle-import:0402-TVS")
      (libsource (lib "eagle-import") (part "DIODE-TVS"))
    )
    (comp (ref "C102")
      (value "8p")
      (footprint "eagle-import:0402-CAP")
      (fields (field (name "PARTNO") "C1005C0G1H080C"))
      (libsource (lib "eagle-import") (part "CAP0402"))
    )
    (comp (ref "C103")
      (value "8p")
      (footprint "eagle-import:0402-CAP")
      (fields (field (name "PARTNO") "C1005C0G1H080C"))
      (libsource (lib "eagle-import") (part "CAP0402"))
    )
    (comp (ref "R102")
      (value "10K")
      (footprint "eagle-import:0402-RES")
      (fields (field (name "PARTNO") "RC0402FR-0710KL"))
      (libsource (lib "eagle-import") (part "RESISTOR0402-RES"))
    )
    (comp (ref "U101")
      (value "STM32F4X7VX")
      (footprint "eagle-import:TQFP100")
      (fields (field (name "PARTNO") "STM32F427VI"))
      (libsource (lib "eagle-import") (part "STM32F4X7VX"))
    )
    (comp (ref "X101")
      (value "3.2x2.5 mm / 24 MHz / 15 ppm")
      (footprint "eagle-import:OSCILLATOR-3.2X2.5")
      (fields (field (name "PARTNO") "NX3225SA-24.000000MHZ"))
      (libsource (lib "eagle-import") (part "OSCILLATOR-3.2X2.5"))
    )
    (comp (ref "C13")
      (value "2u2")
      (footprint "eagle-import:0603-CAP")
      (fields (field (name "PARTNO") "C1608Y5V1C225Z"))
      (libsource (lib "eagle-import") (part "CAP0603"))
    )
    (comp (ref "C14")
      (value "0u1")
      (footprint "eagle-import:0402-CAP")
      (fields (field (name "PARTNO") "CC0402ZRY5V7BB104"))
      (libsource (lib "eagle-import") (part "CAP0402"))
    )
    (comp (ref "J302")
      (value "DF13C-4P-1.25V")
      (footprint "eagle-import:DF13C-4P-1.25V")
      (fields (field (name "PARTNO") "DF13C-4P-1.25V(20)"))
      (libsource (lib "eagle-import") (part "DF13-4P-1.25V"))
    )
    (comp (ref "JX301")
      (value "ARM_MINI_JTAG-SMT")
      (footprint "eagle-import:FTSH-105-01-XXX-DV-K")
      (fields (field (name "BOM") "EXCLUDE") (field (name "PARTNO") "M50-3900542"))
      (libsource (lib "eagle-import") (part "ARM_MINI_JTAG-SMT"))
    )
    (comp (ref "U$3")
      (value "W25Q64FV")
      (footprint "eagle-import:WSON-8-5X6")
      (libsource (lib "eagle-import") (part "W25Q64FV"))
    )
    (comp (ref "U$5")
      (value "NUF2042XV6")
      (footprint "eagle-import:SOT563-6")
      (libsource (lib "eagle-import") (part "NUF2042XV6"))
    )
    (comp (ref "CAN_H")
      (value "PAD.04")
      (footprint "eagle-import:PAD.04X.04")
      (libsource (lib "eagle-import") (part "PAD.04"))
    )
    (comp (ref "CAN_L")
      (value "PAD.04")
      (footprint "eagle-import:PAD.04X.04")
      (libsource (lib "eagle-import") (part "PAD.04"))
    )
    (comp (ref "FMU-BOOT0")
      (value "PAD.04")
      (footprint "eagle-import:PAD.04X.04")
      (libsource (lib "eagle-import") (part "PAD.04"))
    )
    (comp (ref "GND")
      (value "PAD.04")
      (footprint "eagle-import:PAD.04X.04")
      (libsource (lib "eagle-import") (part "PAD.04"))
    )
    (comp (ref "GND.")
      (value "PAD.04")
      (footprint "eagle-import:PAD.04X.04")
      (libsource (lib "eagle-import") (part "PAD.04"))
    )
    (comp (ref "JP1")
      (value "FIDUCIAL1.5X3")
      (footprint "eagle-import:FIDUCIAL-1.5X3")
      (libsource (lib "eagle-import") (part "FIDUCIAL1.5X3"))
    )
    (comp (ref "JP2")
      (value "FIDUCIAL1.5X3")
      (footprint "eagle-import:FIDUCIAL-1.5X3")
      (libsource (lib "eagle-import") (part "FIDUCIAL1.5X3"))
    )
    (comp (ref "M3_MOUNT1101")
      (value "MOUNT-HOLE3.1MM")
      (footprint "eagle-import:MOUNT-HOLE3.1")
      (libsource (lib "eagle-import") (part "MOUNT-HOLE3.1MM"))
    )
    (comp (ref "M3_MOUNT1102")
      (value "MOUNT-HOLE3.1MM")
      (footprint "eagle-import:MOUNT-HOLE3.1")
      (libsource (lib "eagle-import") (part "MOUNT-HOLE3.1MM"))
    )
    (comp (ref "M3_MOUNT1103")
      (value "MOUNT-HOLE3.1MM")
      (footprint "eagle-import:MOUNT-HOLE3.1")
      (libsource (lib "eagle-import") (part "MOUNT-HOLE3.1MM"))
    )
    (comp (ref "M3_MOUNT1104")
      (value "MOUNT-HOLE3.1MM")
      (footprint "eagle-import:MOUNT-HOLE3.1")
      (libsource (lib "eagle-import") (part "MOUNT-HOLE3.1MM"))
    )
    (comp (ref "OSHW_LOGO")
      (value "OSHW-LOGOS")
      (footprint "eagle-import:OSHW-LOGO-S")
      (libsource (lib "eagle-import") (part "OSHW-LOGOS"))
    )
    (comp (ref "S1RX")
      (value "PAD.04")
      (footprint "eagle-import:PAD.04X.04")
      (libsource (lib "eagle-import") (part "PAD.04"))
    )
    (comp (ref "S1TX")
      (value "PAD.04")
      (footprint "eagle-import:PAD.04X.04")
      (libsource (lib "eagle-import") (part "PAD.04"))
    )
    (comp (ref "S2RX")
      (value "PAD.04")
      (footprint "eagle-import:PAD.04X.04")
      (libsource (lib "eagle-import") (part "PAD.04"))
    )
    (comp (ref "S2TX")
      (value "PAD.04")
      (footprint "eagle-import:PAD.04X.04")
      (libsource (lib "eagle-import") (part "PAD.04"))
    )
    (comp (ref "S3RX")
      (value "PAD.04")
      (footprint "eagle-import:PAD.04X.04")
      (libsource (lib "eagle-import") (part "PAD.04"))
    )
    (comp (ref "S3TX")
      (value "PAD.04")
      (footprint "eagle-import:PAD.04X.04")
      (libsource (lib "eagle-import") (part "PAD.04"))
    )
    (comp (ref "VDDA_3V3_SENSORS")
      (value "PAD.04")
      (footprint "eagle-import:PAD.04X.04")
      (libsource (lib "eagle-import") (part "PAD.04"))
    )
    (comp (ref "VDD_3V3")
      (value "PAD.04")
      (footprint "eagle-import:PAD.04X.04")
      (libsource (lib "eagle-import") (part "PAD.04"))
    )
    (comp (ref "D1")
      (value "MSS1P4-M3")
      (footprint "eagle-import:MICROSMP")
      (fields (field (name "PARTNO") "MSS1P4-M3/89A"))
      (libsource (lib "eagle-import") (part "DIODE-SCHOTTKY_MSMP"))
    )
    (comp (ref "D2")
      (value "B340A")
      (footprint "eagle-import:SMA-DIODE")
      (libsource (lib "eagle-import") (part "DIODESMA"))
    )
    (comp (ref "D3")
      (value "DIODESOD")
      (footprint "eagle-import:SOD-323")
      (libsource (lib "eagle-import") (part "DIODESOD"))
    )
    (comp (ref "D5")
      (value "B340A")
      (footprint "eagle-import:SMA-DIODE")
      (libsource (lib "eagle-import") (part "DIODESMA"))
    )
    (comp (ref "JP5")
      (value "M02PTH3")
      (footprint "eagle-import:1X02_LONGPADS")
      (libsource (lib "eagle-import") (part "M02PTH3"))
    )
    (comp (ref "R918")
      (value "10K/0.1%")
      (footprint "eagle-import:0402-RES")
      (fields (field (name "PARTNO") "ERA-2AEB103X"))
      (libsource (lib "eagle-import") (part "RESISTOR0402-RES"))
    )
    (comp (ref "R919")
      (value "10K/0.1%")
      (footprint "eagle-import:0402-RES")
      (fields (field (name "PARTNO") "ERA-2AEB103X"))
      (libsource (lib "eagle-import") (part "RESISTOR0402-RES"))
    )
    (comp (ref "R922")
      (value "10K/0.1%")
      (footprint "eagle-import:0402-RES")
      (fields (field (name "PARTNO") "ERA-2AEB103X"))
      (libsource (lib "eagle-import") (part "RESISTOR0402-RES"))
    )
    (comp (ref "J802")
      (value "DF13C-3P-1.25V")
      (footprint "eagle-import:DF13C-3P-1.25V")
      (fields (field (name "PARTNO") "DF13C-3P-1.25V(20)"))
      (libsource (lib "eagle-import") (part "DF13-3P-1.25V"))
    )
    (comp (ref "LED701")
      (value "AMBER")
      (footprint "eagle-import:0603-LED")
      (fields (field (name "PARTNO") "APTD1608SECK"))
      (libsource (lib "eagle-import") (part "LED0603"))
    )
    (comp (ref "LED704")
      (value "GREEN")
      (footprint "eagle-import:0603-LED")
      (fields (field (name "PARTNO") "APTD1608CGCK"))
      (libsource (lib "eagle-import") (part "LED0603"))
    )
    (comp (ref "LED705")
      (value "BLUE")
      (footprint "eagle-import:0603-LED")
      (fields (field (name "PARTNO") "APTD1608QBC/D"))
      (libsource (lib "eagle-import") (part "LED0603"))
    )
    (comp (ref "R3")
      (value "220R")
      (footprint "eagle-import:0402-RES")
      (fields (field (name "PARTNO") "RC0402FR-07220RL"))
      (libsource (lib "eagle-import") (part "RESISTOR0402-RES"))
    )
    (comp (ref "R707")
      (value "220R")
      (footprint "eagle-import:0402-RES")
      (fields (field (name "PARTNO") "RC0402FR-07220RL"))
      (libsource (lib "eagle-import") (part "RESISTOR0402-RES"))
    )
    (comp (ref "R710")
      (value "47R")
      (footprint "eagle-import:0402-RES")
      (fields (field (name "PARTNO") "RC0402JR-0747RL"))
      (libsource (lib "eagle-import") (part "RESISTOR0402-RES"))
    )
    (comp (ref "R711")
      (value "220R")
      (footprint "eagle-import:0402-RES")
      (fields (field (name "PARTNO") "RC0402FR-07220RL"))
      (libsource (lib "eagle-import") (part "RESISTOR0402-RES"))
    )
    (comp (ref "R712")
      (value "220R")
      (footprint "eagle-import:0402-RES")
      (fields (field (name "PARTNO") "RC0402FR-07220RL"))
      (libsource (lib "eagle-import") (part "RESISTOR0402-RES"))
    )
    (comp (ref "R713")
      (value "1K5")
      (footprint "eagle-import:0402-RES")
      (fields (field (name "PARTNO") "RC0402FR-071K5L"))
      (libsource (lib "eagle-import") (part "RESISTOR0402-RES"))
    )
    (comp (ref "U$701")
      (value "PESD0402-140")
      (footprint "eagle-import:0402-TVS")
      (libsource (lib "eagle-import") (part "DIODE-TVS"))
    )
    (comp (ref "C2")
      (value "0u1")
      (footprint "eagle-import:0402-CAP")
      (fields (field (name "PARTNO") "CC0402ZRY5V7BB104"))
      (libsource (lib "eagle-import") (part "CAP0402"))
    )
    (comp (ref "C3")
      (value "0u1")
      (footprint "eagle-import:0402-CAP")
      (fields (field (name "PARTNO") "CC0402ZRY5V7BB104"))
      (libsource (lib "eagle-import") (part "CAP0402"))
    )
    (comp (ref "C4")
      (value "0u1")
      (footprint "eagle-import:0402-CAP")
      (fields (field (name "PARTNO") "CC0402ZRY5V7BB104"))
      (libsource (lib "eagle-import") (part "CAP0402"))
    )
    (comp (ref "C402")
      (value "0u1")
      (footprint "eagle-import:0402-CAP")
      (fields (field (name "PARTNO") "CC0402ZRY5V7BB104"))
      (libsource (lib "eagle-import") (part "CAP0402"))
    )
    (comp (ref "J2")
      (value "DF13-4P-1.25V")
      (footprint "eagle-import:DF13C-4P-1.25V")
      (fields (field (name "PARTNO") "DF13C-4P-1.25V(20)"))
      (libsource (lib "eagle-import") (part "DF13-4P-1.25V"))
    )
    (comp (ref "J3")
      (value "DF13C-4P-1.25V")
      (footprint "eagle-import:DF13C-4P-1.25V")
      (fields (field (name "PARTNO") "DF13C-4P-1.25V(20)"))
      (libsource (lib "eagle-import") (part "DF13-4P-1.25V"))
    )
    (comp (ref "J401")
      (value "DF13C-4P-1.25V")
      (footprint "eagle-import:DF13C-4P-1.25V")
      (fields (field (name "PARTNO") "DF13C-4P-1.25V(20)"))
      (libsource (lib "eagle-import") (part "DF13-4P-1.25V"))
    )
    (comp (ref "J403")
      (value "DF13C-7P-1.25V")
      (footprint "eagle-import:DF13C-7P-1.25V")
      (fields (field (name "PARTNO") "DF13C-7P-1.25V(20)"))
      (libsource (lib "eagle-import") (part "DF13-7P-1.25V"))
    )
    (comp (ref "J405")
      (value "DF13C-4P-1.25V")
      (footprint "eagle-import:DF13C-4P-1.25V")
      (fields (field (name "PARTNO") "DF13C-4P-1.25V(20)"))
      (libsource (lib "eagle-import") (part "DF13-4P-1.25V"))
    )
    (comp (ref "L4")
      (value "KNH16C104DA5TS")
      (footprint "eagle-import:KYOCERA-KNH16-DA")
      (libsource (lib "eagle-import") (part "KNH16C104DA5TS"))
    )
    (comp (ref "L5")
      (value "KNH16C104DA5TS")
      (footprint "eagle-import:KYOCERA-KNH16-DA")
      (libsource (lib "eagle-import") (part "KNH16C104DA5TS"))
    )
    (comp (ref "L6")
      (value "NUF8402MN")
      (footprint "eagle-import:DFN16-THIN")
      (libsource (lib "eagle-import") (part "NUF8402MN"))
    )
    (comp (ref "L7")
      (value "KNH16C104DA5TS")
      (footprint "eagle-import:KYOCERA-KNH16-DA")
      (libsource (lib "eagle-import") (part "KNH16C104DA5TS"))
    )
    (comp (ref "L402")
      (value "KNH16C104DA5TS")
      (footprint "eagle-import:KYOCERA-KNH16-DA")
      (libsource (lib "eagle-import") (part "KNH16C104DA5TS"))
    )
    (comp (ref "L403")
      (value "KNH16C104DA5TS")
      (footprint "eagle-import:KYOCERA-KNH16-DA")
      (libsource (lib "eagle-import") (part "KNH16C104DA5TS"))
    )
    (comp (ref "R1")
      (value "1K5")
      (footprint "eagle-import:0402-RES")
      (fields (field (name "PARTNO") "RC0402FR-071K5L"))
      (libsource (lib "eagle-import") (part "RESISTOR0402-RES"))
    )
    (comp (ref "R2")
      (value "1K5")
      (footprint "eagle-import:0402-RES")
      (fields (field (name "PARTNO") "RC0402FR-071K5L"))
      (libsource (lib "eagle-import") (part "RESISTOR0402-RES"))
    )
    (comp (ref "R4")
      (value "120R")
      (footprint "eagle-import:0402-RES")
      (fields (field (name "PARTNO") "RC0402FR-07120RL"))
      (libsource (lib "eagle-import") (part "RESISTOR0402-RES"))
    )
    (comp (ref "R401")
      (value "1K5")
      (footprint "eagle-import:0402-RES")
      (fields (field (name "PARTNO") "RC0402FR-071K5L"))
      (libsource (lib "eagle-import") (part "RESISTOR0402-RES"))
    )
    (comp (ref "R402")
      (value "1K5")
      (footprint "eagle-import:0402-RES")
      (fields (field (name "PARTNO") "RC0402FR-071K5L"))
      (libsource (lib "eagle-import") (part "RESISTOR0402-RES"))
    )
    (comp (ref "R407")
      (value "10K/0.1%")
      (footprint "eagle-import:0402-RES")
      (fields (field (name "PARTNO") "ERA-2AEB103X"))
      (libsource (lib "eagle-import") (part "RESISTOR0402-RES"))
    )
    (comp (ref "R408")
      (value "10K/0.1%")
      (footprint "eagle-import:0402-RES")
      (fields (field (name "PARTNO") "ERA-2AEB103X"))
      (libsource (lib "eagle-import") (part "RESISTOR0402-RES"))
    )
    (comp (ref "R409")
      (value "120R")
      (footprint "eagle-import:0402-RES")
      (fields (field (name "PARTNO") "RC0402FR-07120RL"))
      (libsource (lib "eagle-import") (part "RESISTOR0402-RES"))
    )
    (comp (ref "SJ1")
      (value "SOLDERJUMPERTRACE")
      (footprint "eagle-import:SJ_2S-TRACE")
      (libsource (lib "eagle-import") (part "SOLDERJUMPERTRACE"))
    )
    (comp (ref "SJ2")
      (value "SOLDERJUMPERTRACE")
      (footprint "eagle-import:SJ_2S-TRACE")
      (libsource (lib "eagle-import") (part "SOLDERJUMPERTRACE"))
    )
    (comp (ref "U$1")
      (value "HEADER-3X1BOARDEDGE-SHORT")
      (footprint "eagle-import:HEADER_3X01_SMD_H_BOARD_EDGE_SHORT")
      (libsource (lib "eagle-import") (part "HEADER-3X1BOARDEDGE-SHORT"))
    )
    (comp (ref "U$4")
      (value "PESD0402-140")
      (footprint "eagle-import:0402-TVS")
      (libsource (lib "eagle-import") (part "DIODE-TVS"))
    )
    (comp (ref "U$7")
      (value "PESD0402-140")
      (footprint "eagle-import:0402-TVS")
      (libsource (lib "eagle-import") (part "DIODE-TVS"))
    )
    (comp (ref "U$401")
      (value "PESD0402-140")
      (footprint "eagle-import:0402-TVS")
      (libsource (lib "eagle-import") (part "DIODE-TVS"))
    )
    (comp (ref "U$402")
      (value "PESD0402-140")
      (footprint "eagle-import:0402-TVS")
      (libsource (lib "eagle-import") (part "DIODE-TVS"))
    )
    (comp (ref "U$404")
      (value "PESD0402-140")
      (footprint "eagle-import:0402-TVS")
      (libsource (lib "eagle-import") (part "DIODE-TVS"))
    )
    (comp (ref "U2")
      (value "MAX3051")
      (footprint "eagle-import:SOT23-8")
      (fields (field (name "PARTNO") "MAX3051EKA"))
      (libsource (lib "eagle-import") (part "MAX3051MAX3051EKA"))
    )
    (comp (ref "U401")
      (value "MAX3051")
      (footprint "eagle-import:SOT23-8")
      (fields (field (name "PARTNO") "MAX3051EKA"))
      (libsource (lib "eagle-import") (part "MAX3051MAX3051EKA"))
    )
    (comp (ref "C5")
      (value "0u1")
      (footprint "eagle-import:0402-CAP")
      (fields (field (name "PARTNO") "CC0402ZRY5V7BB104"))
      (libsource (lib "eagle-import") (part "CAP0402"))
    )
    (comp (ref "C505")
      (value "10n")
      (footprint "eagle-import:0402-CAP")
      (fields (field (name "PARTNO") "CC0402KRX7R7BB103"))
      (libsource (lib "eagle-import") (part "CAP0402"))
    )
    (comp (ref "C506")
      (value "10u/10V")
      (footprint "eagle-import:0805-CAP")
      (fields (field (name "PARTNO") "CC0805ZKY5V6BB106"))
      (libsource (lib "eagle-import") (part "CAP0805"))
    )
    (comp (ref "U$2")
      (value "MAX21100")
      (footprint "eagle-import:16LGA-3X3")
      (libsource (lib "eagle-import") (part "MAX21100"))
    )
    (comp (ref "J1")
      (value "SERVO_HEADER-3X8")
      (footprint "eagle-import:3X8RA_SERVO")
      (libsource (lib "eagle-import") (part "SERVO_HEADER-3X8"))
    )
    (comp (ref "L1")
      (value "NUF8402MN")
      (footprint "eagle-import:DFN16-THIN")
      (libsource (lib "eagle-import") (part "NUF8402MN"))
    )
    (comp (ref "C1")
      (value "22uF")
      (footprint "eagle-import:1210")
      (libsource (lib "eagle-import") (part "22UF-16V-20%-(1210)"))
    )
    (comp (ref "C6")
      (value "0u1")
      (footprint "eagle-import:0402-CAP")
      (fields (field (name "PARTNO") "CC0402ZRY5V7BB104"))
      (libsource (lib "eagle-import") (part "CAP0402"))
    )
    (comp (ref "C7")
      (value "0u1")
      (footprint "eagle-import:0402-CAP")
      (fields (field (name "PARTNO") "CC0402ZRY5V7BB104"))
      (libsource (lib "eagle-import") (part "CAP0402"))
    )
    (comp (ref "C8")
      (value "22uF")
      (footprint "eagle-import:1210")
      (libsource (lib "eagle-import") (part "22UF-16V-20%-(1210)"))
    )
    (comp (ref "C9")
      (value "22uF")
      (footprint "eagle-import:1210")
      (libsource (lib "eagle-import") (part "22UF-16V-20%-(1210)"))
    )
    (comp (ref "C10")
      (value "22uF")
      (footprint "eagle-import:1210")
      (libsource (lib "eagle-import") (part "22UF-16V-20%-(1210)"))
    )
    (comp (ref "C11")
      (value "0u1")
      (footprint "eagle-import:0402-CAP")
      (fields (field (name "PARTNO") "CC0402ZRY5V7BB104"))
      (libsource (lib "eagle-import") (part "CAP0402"))
    )
    (comp (ref "C12")
      (value "0u1")
      (footprint "eagle-import:0402-CAP")
      (fields (field (name "PARTNO") "CC0402ZRY5V7BB104"))
      (libsource (lib "eagle-import") (part "CAP0402"))
    )
    (comp (ref "R6")
      (value "10K")
      (footprint "eagle-import:0402-RES")
      (fields (field (name "PARTNO") "RC0402FR-0710KL"))
      (libsource (lib "eagle-import") (part "RESISTOR0402-RES"))
    )
    (comp (ref "U$15")
      (value "TPS6303X")
      (footprint "eagle-import:PWSON10")
      (libsource (lib "eagle-import") (part "TPS6303X"))
    )
    (comp (ref "U$16")
      (value "XFL4020-222MEB")
      (footprint "eagle-import:XFL4020")
      (libsource (lib "eagle-import") (part "XFL4020-222MEB"))
    )
    (comp (ref "C15")
      (value "0u1")
      (footprint "eagle-import:0402-CAP")
      (fields (field (name "PARTNO") "CC0402ZRY5V7BB104"))
      (libsource (lib "eagle-import") (part "CAP0402"))
    )
    (comp (ref "C601")
      (value "2u2")
      (footprint "eagle-import:0603-CAP")
      (fields (field (name "PARTNO") "C1608Y5V1C225Z"))
      (libsource (lib "eagle-import") (part "CAP0603"))
    )
    (comp (ref "C602")
      (value "10n")
      (footprint "eagle-import:0402-CAP")
      (fields (field (name "PARTNO") "CC0402KRX7R7BB103"))
      (libsource (lib "eagle-import") (part "CAP0402"))
    )
    (comp (ref "C603")
      (value "1u0")
      (footprint "eagle-import:0603-CAP")
      (fields (field (name "PARTNO") "CC0603ZRY5V7BB105"))
      (libsource (lib "eagle-import") (part "CAP0603"))
    )
    (comp (ref "C604")
      (value "10u/10V")
      (footprint "eagle-import:0805-CAP")
      (fields (field (name "PARTNO") "CC0805ZKY5V6BB106"))
      (libsource (lib "eagle-import") (part "CAP0805"))
    )
    (comp (ref "C605")
      (value "1u0")
      (footprint "eagle-import:0603-CAP")
      (fields (field (name "PARTNO") "CC0603ZRY5V7BB105"))
      (libsource (lib "eagle-import") (part "CAP0603"))
    )
    (comp (ref "C606")
      (value "0u1")
      (footprint "eagle-import:0402-CAP")
      (fields (field (name "PARTNO") "CC0402ZRY5V7BB104"))
      (libsource (lib "eagle-import") (part "CAP0402"))
    )
    (comp (ref "C607")
      (value "0u1")
      (footprint "eagle-import:0402-CAP")
      (fields (field (name "PARTNO") "CC0402ZRY5V7BB104"))
      (libsource (lib "eagle-import") (part "CAP0402"))
    )
    (comp (ref "C608")
      (value "0u1")
      (footprint "eagle-import:0402-CAP")
      (fields (field (name "PARTNO") "CC0402ZRY5V7BB104"))
      (libsource (lib "eagle-import") (part "CAP0402"))
    )
    (comp (ref "C609")
      (value "0u1")
      (footprint "eagle-import:0402-CAP")
      (fields (field (name "PARTNO") "CC0402ZRY5V7BB104"))
      (libsource (lib "eagle-import") (part "CAP0402"))
    )
    (comp (ref "C610")
      (value "0u1")
      (footprint "eagle-import:0402-CAP")
      (fields (field (name "PARTNO") "CC0402ZRY5V7BB104"))
      (libsource (lib "eagle-import") (part "CAP0402"))
    )
    (comp (ref "C611")
      (value "2u2")
      (footprint "eagle-import:0603-CAP")
      (fields (field (name "PARTNO") "C1608Y5V1C225Z"))
      (libsource (lib "eagle-import") (part "CAP0603"))
    )
    (comp (ref "C612")
      (value "0u1")
      (footprint "eagle-import:0402-CAP")
      (fields (field (name "PARTNO") "CC0402ZRY5V7BB104"))
      (libsource (lib "eagle-import") (part "CAP0402"))
    )
    (comp (ref "C613")
      (value "2u2")
      (footprint "eagle-import:0603-CAP")
      (fields (field (name "PARTNO") "C1608Y5V1C225Z"))
      (libsource (lib "eagle-import") (part "CAP0603"))
    )
    (comp (ref "C1001")
      (value "1u0")
      (footprint "eagle-import:0603-CAP")
      (fields (field (name "PARTNO") "CC0603ZRY5V7BB105"))
      (libsource (lib "eagle-import") (part "CAP0603"))
    )
    (comp (ref "C1002")
      (value "10n")
      (footprint "eagle-import:0402-CAP")
      (fields (field (name "PARTNO") "CC0402KRX7R7BB103"))
      (libsource (lib "eagle-import") (part "CAP0402"))
    )
    (comp (ref "C1003")
      (value "1u0")
      (footprint "eagle-import:0603-CAP")
      (fields (field (name "PARTNO") "CC0603ZRY5V7BB105"))
      (libsource (lib "eagle-import") (part "CAP0603"))
    )
    (comp (ref "C1004")
      (value "1u0")
      (footprint "eagle-import:0603-CAP")
      (fields (field (name "PARTNO") "CC0603ZRY5V7BB105"))
      (libsource (lib "eagle-import") (part "CAP0603"))
    )
    (comp (ref "R5")
      (value "10K")
      (footprint "eagle-import:0402-RES")
      (fields (field (name "PARTNO") "RC0402FR-0710KL"))
      (libsource (lib "eagle-import") (part "RESISTOR0402-RES"))
    )
    (comp (ref "R603")
      (value "10K")
      (footprint "eagle-import:0402-RES")
      (fields (field (name "PARTNO") "RC0402FR-0710KL"))
      (libsource (lib "eagle-import") (part "RESISTOR0402-RES"))
    )
    (comp (ref "R606")
      (value "25K")
      (footprint "eagle-import:0402-RES")
      (fields (field (name "PARTNO") "RMCF0402FT25K5"))
      (libsource (lib "eagle-import") (part "RESISTOR0402-RES"))
    )
    (comp (ref "R607")
      (value "10K")
      (footprint "eagle-import:0402-RES")
      (fields (field (name "PARTNO") "RC0402FR-0710KL"))
      (libsource (lib "eagle-import") (part "RESISTOR0402-RES"))
    )
    (comp (ref "R608")
      (value "1K")
      (footprint "eagle-import:0402-RES")
      (fields (field (name "PARTNO") "RC0402FR-071KL"))
      (libsource (lib "eagle-import") (part "RESISTOR0402-RES"))
    )
    (comp (ref "R609")
      (value "10K/0.1%")
      (footprint "eagle-import:0402-RES")
      (fields (field (name "PARTNO") "ERA-2AEB103X"))
      (libsource (lib "eagle-import") (part "RESISTOR0402-RES"))
    )
    (comp (ref "R610")
      (value "10K/0.1%")
      (footprint "eagle-import:0402-RES")
      (fields (field (name "PARTNO") "ERA-2AEB103X"))
      (libsource (lib "eagle-import") (part "RESISTOR0402-RES"))
    )
    (comp (ref "R611")
      (value "10K")
      (footprint "eagle-import:0402-RES")
      (fields (field (name "PARTNO") "RC0402FR-0710KL"))
      (libsource (lib "eagle-import") (part "RESISTOR0402-RES"))
    )
    (comp (ref "R1002")
      (value "10K")
      (footprint "eagle-import:0402-RES")
      (fields (field (name "PARTNO") "RC0402FR-0710KL"))
      (libsource (lib "eagle-import") (part "RESISTOR0402-RES"))
    )
    (comp (ref "S601")
      (value "RESET")
      (footprint "eagle-import:EVQP7J01K")
      (fields (field (name "PARTNO") "EVQP7J01K"))
      (libsource (lib "eagle-import") (part "SWITCH-MOMENTARY-2"))
    )
    (comp (ref "U$604")
      (value "BQ24315")
      (footprint "eagle-import:QFN8-DSG")
      (fields (field (name "PARTNO") "BQ24315DSGR"))
      (libsource (lib "eagle-import") (part "BQ24315"))
    )
    (comp (ref "U$605")
      (value "MIC5332")
      (footprint "eagle-import:MLF-8-EPAD")
      (fields (field (name "PARTNO") "MIC5332-SSYMT"))
      (libsource (lib "eagle-import") (part "MIC5332"))
    )
    (comp (ref "U$1002")
      (value "MIC5332")
      (footprint "eagle-import:MLF-8-EPAD")
      (fields (field (name "PARTNO") "MIC5332-SSYMT"))
      (libsource (lib "eagle-import") (part "MIC5332"))
    )
  )
  (nets
    (net (code "1") (name "ACCEL_DRDY") (class "Default")
      (node (ref "U$2") (pin "11") (pinfunction "INT1_11") (pintype "bidirectional"))
      (node (ref "U101") (pin "90") (pinfunction "PB4_90") (pintype "bidirectional"))
    )
    (net (code "2") (name "ALARM") (class "Default")
      (node (ref "U101") (pin "77") (pinfunction "PA15_77") (pintype "bidirectional"))
    )
    (net (code "3") (name "CAN1_H") (class "Default")
      (node (ref "CAN_H") (pin "P$1") (pinfunction "P$1_P$1") (pintype "passive"))
      (node (ref "J405") (pin "P$2") (pinfunction "2_P$2") (pintype "passive"))
      (node (ref "R409") (pin "P$1") (pinfunction "1_P$1") (pintype "passive"))
      (node (ref "U401") (pin "7") (pinfunction "CANH_7") (pintype "bidirectional"))
    )
    (net (code "4") (name "CAN1_L") (class "Default")
      (node (ref "CAN_L") (pin "P$1") (pinfunction "P$1_P$1") (pintype "passive"))
      (node (ref "J405") (pin "P$3") (pinfunction "3_P$3") (pintype "passive"))
      (node (ref "SJ1") (pin "2") (pinfunction "2_2") (pintype "passive"))
      (node (ref "U401") (pin "6") (pinfunction "CANL_6") (pintype "bidirectional"))
    )
    (net (code "5") (name "CAN1_RX") (class "Default")
      (node (ref "U101") (pin "81") (pinfunction "PD0_81") (pintype "bidirectional"))
      (node (ref "U401") (pin "4") (pinfunction "DOUT_4") (pintype "output"))
    )
    (net (code "6") (name "CAN1_TX") (class "Default")
      (node (ref "U101") (pin "82") (pinfunction "PD1_82") (pintype "bidirectional"))
      (node (ref "U401") (pin "1") (pinfunction "DIN_1") (pintype "input"))
    )
    (net (code "7") (name "CAN2_RX") (class "Default")
      (node (ref "U101") (pin "51") (pinfunction "PB12_51") (pintype "bidirectional"))
      (node (ref "U2") (pin "4") (pinfunction "DOUT_4") (pintype "output"))
    )
    (net (code "8") (name "CAN2_TX") (class "Default")
      (node (ref "U101") (pin "92") (pinfunction "PB6_92") (pintype "bidirectional"))
      (node (ref "U2") (pin "1") (pinfunction "DIN_1") (pintype "input"))
    )
    (net (code "9") (name "FMU-BOOT0") (class "Default")
      (node (ref "FMU-BOOT0") (pin "P$1") (pinfunction "P$1_P$1") (pintype "passive"))
      (node (ref "R611") (pin "P$2") (pinfunction "2_P$2") (pintype "passive"))
      (node (ref "U101") (pin "94") (pinfunction "BOOT0_94") (pintype "input"))
    )
    (net (code "10") (name "FMU-CH1") (class "Default")
      (node (ref "L1") (pin "P$1") (pinfunction "P$1_P$1") (pintype "bidirectional"))
      (node (ref "U101") (pin "45") (pinfunction "PE14_45") (pintype "bidirectional"))
    )
    (net (code "11") (name "FMU-CH2") (class "Default")
      (node (ref "L1") (pin "P$2") (pinfunction "P$1_P$2") (pintype "bidirectional"))
      (node (ref "U101") (pin "44") (pinfunction "PE13_44") (pintype "bidirectional"))
    )
    (net (code "12") (name "FMU-CH3") (class "Default")
      (node (ref "L1") (pin "P$3") (pinfunction "P$1_P$3") (pintype "bidirectional"))
      (node (ref "U101") (pin "42") (pinfunction "PE11_42") (pintype "bidirectional"))
    )
    (net (code "13") (name "FMU-CH4") (class "Default")
      (node (ref "L1") (pin "P$4") (pinfunction "P$1_P$4") (pintype "bidirectional"))
      (node (ref "U101") (pin "40") (pinfunction "PE9_40") (pintype "bidirectional"))
    )
    (net (code "14") (name "FMU-CH5") (class "Default")
      (node (ref "L1") (pin "P$5") (pinfunction "P$1_P$5") (pintype "bidirectional"))
      (node (ref "U101") (pin "60") (pinfunction "PD13_60") (pintype "bidirectional"))
    )
    (net (code "15") (name "FMU-CH6") (class "Default")
      (node (ref "L1") (pin "P$6") (pinfunction "P$1_P$6") (pintype "bidirectional"))
      (node (ref "U101") (pin "62") (pinfunction "PD15_62") (pintype "bidirectional"))
    )
    (net (code "16") (name "FMU-CH7") (class "Default")
      (node (ref "L1") (pin "P$7") (pinfunction "P$1_P$7") (pintype "bidirectional"))
      (node (ref "U101") (pin "24") (pinfunction "PA1_24") (pintype "bidirectional"))
    )
    (net (code "17") (name "FMU-CH8") (class "Default")
      (node (ref "L1") (pin "P$8") (pinfunction "P$1_P$8") (pintype "bidirectional"))
      (node (ref "U101") (pin "61") (pinfunction "PD14_61") (pintype "bidirectional"))
    )
    (net (code "18") (name "FMU-CH9") (class "Default")
      (node (ref "U101") (pin "25") (pinfunction "PA2_25") (pintype "bidirectional"))
    )
    (net (code "19") (name "FMU-CH10") (class "Default")
      (node (ref "U101") (pin "26") (pinfunction "PA3_26") (pintype "bidirectional"))
    )
    (net (code "20") (name "FMU-I2C1_SCL") (class "Default")
      (node (ref "L6") (pin "P$8") (pinfunction "P$1_P$8") (pintype "bidirectional"))
      (node (ref "R401") (pin "P$1") (pinfunction "1_P$1") (pintype "passive"))
      (node (ref "U101") (pin "95") (pinfunction "PB8_95") (pintype "bidirectional"))
    )
    (net (code "21") (name "FMU-I2C1_SDA") (class "Default")
      (node (ref "L6") (pin "P$7") (pinfunction "P$1_P$7") (pintype "bidirectional"))
      (node (ref "R402") (pin "P$1") (pinfunction "1_P$1") (pintype "passive"))
      (node (ref "U101") (pin "96") (pinfunction "PB9_96") (pintype "bidirectional"))
    )
    (net (code "22") (name "FMU-I2C2_SCL") (class "Default")
      (node (ref "L6") (pin "P$2") (pinfunction "P$1_P$2") (pintype "bidirectional"))
      (node (ref "R1") (pin "P$1") (pinfunction "1_P$1") (pintype "passive"))
      (node (ref "U101") (pin "47") (pinfunction "PB10_47") (pintype "bidirectional"))
    )
    (net (code "23") (name "FMU-I2C2_SDA") (class "Default")
      (node (ref "L6") (pin "P$1") (pinfunction "P$1_P$1") (pintype "bidirectional"))
      (node (ref "R2") (pin "P$1") (pinfunction "1_P$1") (pintype "passive"))
      (node (ref "U101") (pin "48") (pinfunction "PB11_48") (pintype "bidirectional"))
    )
    (net (code "24") (name "FMU-LED_BLUE") (class "Default")
      (node (ref "R712") (pin "P$1") (pinfunction "1_P$1") (pintype "passive"))
    )
    (net (code "25") (name "FMU-LED_SAFETY") (class "Default")
      (node (ref "R710") (pin "P$2") (pinfunction "2_P$2") (pintype "passive"))
    )
    (net (code "26") (name "FMU-SWCLK") (class "Default")
      (node (ref "JX301") (pin "4") (pinfunction "S_4") (pintype "passive"))
      (node (ref "U101") (pin "76") (pinfunction "PA14_76") (pintype "bidirectional"))
    )
    (net (code "27") (name "FMU-SWDIO") (class "Default")
      (node (ref "JX301") (pin "2") (pinfunction "S_2") (pintype "passive"))
      (node (ref "U101") (pin "72") (pinfunction "PA13_72") (pintype "bidirectional"))
    )
    (net (code "28") (name "FMU-SWO") (class "Default")
      (node (ref "JX301") (pin "6") (pinfunction "S_6") (pintype "passive"))
      (node (ref "U101") (pin "89") (pinfunction "PB3_89") (pintype "bidirectional"))
    )
    (net (code "29") (name "FMU-UART7_RX") (class "Default")
      (node (ref "L3") (pin "P$5") (pinfunction "P$1_P$5") (pintype "bidirectional"))
      (node (ref "U101") (pin "38") (pinfunction "PE7_38") (pintype "bidirectional"))
    )
    (net (code "30") (name "FMU-UART7_TX") (class "Default")
      (node (ref "L3") (pin "P$6") (pinfunction "P$1_P$6") (pintype "bidirectional"))
      (node (ref "U101") (pin "39") (pinfunction "PE8_39") (pintype "bidirectional"))
    )
    (net (code "31") (name "FMU-UART8_RX") (class "Default")
      (node (ref "U101") (pin "97") (pinfunction "PE0_97") (pintype "bidirectional"))
    )
    (net (code "32") (name "FMU-UART8_TX") (class "Default")
      (node (ref "U101") (pin "98") (pinfunction "PE1_98") (pintype "bidirectional"))
    )
    (net (code "33") (name "FMU-USART2_CTS") (class "Default")
      (node (ref "L2") (pin "P$8") (pinfunction "P$1_P$8") (pintype "bidirectional"))
      (node (ref "U101") (pin "84") (pinfunction "PD3_84") (pintype "bidirectional"))
    )
    (net (code "34") (name "FMU-USART2_RTS") (class "Default")
      (node (ref "L2") (pin "P$7") (pinfunction "P$1_P$7") (pintype "bidirectional"))
      (node (ref "U101") (pin "85") (pinfunction "PD4_85") (pintype "bidirectional"))
    )
    (net (code "35") (name "FMU-USART2_RX") (class "Default")
      (node (ref "L2") (pin "P$5") (pinfunction "P$1_P$5") (pintype "bidirectional"))
      (node (ref "U101") (pin "87") (pinfunction "PD6_87") (pintype "bidirectional"))
    )
    (net (code "36") (name "FMU-USART2_TX") (class "Default")
      (node (ref "L2") (pin "P$6") (pinfunction "P$1_P$6") (pintype "bidirectional"))
      (node (ref "U101") (pin "86") (pinfunction "PD5_86") (pintype "bidirectional"))
    )
    (net (code "37") (name "FMU-USART3_CTS") (class "Default")
      (node (ref "L2") (pin "P$2") (pinfunction "P$1_P$2") (pintype "bidirectional"))
      (node (ref "U101") (pin "58") (pinfunction "PD11_58") (pintype "bidirectional"))
    )
    (net (code "38") (name "FMU-USART3_RTS") (class "Default")
      (node (ref "L2") (pin "P$1") (pinfunction "P$1_P$1") (pintype "bidirectional"))
      (node (ref "U101") (pin "59") (pinfunction "PD12_59") (pintype "bidirectional"))
    )
    (net (code "39") (name "FMU-USART3_RX") (class "Default")
      (node (ref "L2") (pin "P$3") (pinfunction "P$1_P$3") (pintype "bidirectional"))
      (node (ref "U101") (pin "56") (pinfunction "PD9_56") (pintype "bidirectional"))
    )
    (net (code "40") (name "FMU-USART3_TX") (class "Default")
      (node (ref "L2") (pin "P$4") (pinfunction "P$1_P$4") (pintype "bidirectional"))
      (node (ref "U101") (pin "55") (pinfunction "PD8_55") (pintype "bidirectional"))
    )
    (net (code "41") (name "FMU-VDD_3V3") (class "Default")
      (node (ref "C13") (pin "P$1") (pinfunction "1_P$1") (pintype "passive"))
      (node (ref "C14") (pin "P$1") (pinfunction "1_P$1") (pintype "passive"))
      (node (ref "C15") (pin "P$1") (pinfunction "1_P$1") (pintype "passive"))
      (node (ref "C4") (pin "P$1") (pinfunction "1_P$1") (pintype "passive"))
      (node (ref "C402") (pin "P$1") (pinfunction "1_P$1") (pintype "passive"))
      (node (ref "C603") (pin "P$1") (pinfunction "1_P$1") (pintype "passive"))
      (node (ref "C604") (pin "P$1") (pinfunction "1_P$1") (pintype "passive"))
      (node (ref "C606") (pin "P$1") (pinfunction "1_P$1") (pintype "passive"))
      (node (ref "C607") (pin "P$1") (pinfunction "1_P$1") (pintype "passive"))
      (node (ref "C608") (pin "P$1") (pinfunction "1_P$1") (pintype "passive"))
      (node (ref "C610") (pin "P$1") (pinfunction "1_P$1") (pintype "passive"))
      (node (ref "C612") (pin "P$1") (pinfunction "1_P$1") (pintype "passive"))
      (node (ref "J802") (pin "P$1") (pinfunction "1_P$1") (pintype "passive"))
      (node (ref "JX301") (pin "1") (pinfunction "S_1") (pintype "passive"))
      (node (ref "R1") (pin "P$2") (pinfunction "2_P$2") (pintype "passive"))
      (node (ref "R2") (pin "P$2") (pinfunction "2_P$2") (pintype "passive"))
      (node (ref "R401") (pin "P$2") (pinfunction "2_P$2") (pintype "passive"))
      (node (ref "R402") (pin "P$2") (pinfunction "2_P$2") (pintype "passive"))
      (node (ref "R608") (pin "P$2") (pinfunction "2_P$2") (pintype "passive"))
      (node (ref "U$3") (pin "8") (pinfunction "VCC_8") (pintype "bidirectional"))
      (node (ref "U$605") (pin "7") (pinfunction "VOUT2_7") (pintype "bidirectional"))
      (node (ref "U$701") (pin "C") (pinfunction "C_C") (pintype "passive"))
      (node (ref "U101") (pin "100") (pinfunction "VDD_100") (pintype "power_in"))
      (node (ref "U101") (pin "11") (pinfunction "VDD_11") (pintype "power_in"))
      (node (ref "U101") (pin "19") (pinfunction "VDD_19") (pintype "power_in"))
      (node (ref "U101") (pin "21") (pinfunction "VREF+_21") (pintype "input"))
      (node (ref "U101") (pin "22") (pinfunction "VDDA_22") (pintype "power_in"))
      (node (ref "U101") (pin "28") (pinfunction "VDD_28") (pintype "power_in"))
      (node (ref "U101") (pin "50") (pinfunction "VDD_50") (pintype "power_in"))
      (node (ref "U101") (pin "75") (pinfunction "VDD_75") (pintype "power_in"))
      (node (ref "U2") (pin "3") (pinfunction "VCC_3") (pintype "input"))
      (node (ref "U401") (pin "3") (pinfunction "VCC_3") (pintype "input"))
      (node (ref "VDD_3V3") (pin "P$1") (pinfunction "P$1_P$1") (pintype "passive"))
    )
    (net (code "42") (name "FMU-~{RESET}") (class "Default")
      (node (ref "C609") (pin "P$2") (pinfunction "2_P$2") (pintype "passive"))
      (node (ref "S601") (pin "A1") (pinfunction "1_A1") (pintype "passive"))
      (node (ref "U$605") (pin "3") (pinfunction "POR2_3") (pintype "bidirectional"))
      (node (ref "U101") (pin "14") (pinfunction "NRST_14") (pintype "input"))
    )
    (net (code "43") (name "FMU_AUX_ADC1") (class "Default")
      (node (ref "R408") (pin "P$1") (pinfunction "1_P$1") (pintype "passive"))
      (node (ref "U101") (pin "18") (pinfunction "PC3_18") (pintype "bidirectional"))
    )
    (net (code "44") (name "FMU_AUX_ADC2") (class "Default")
      (node (ref "R407") (pin "P$1") (pinfunction "1_P$1") (pintype "passive"))
      (node (ref "U101") (pin "33") (pinfunction "PC4_33") (pintype "bidirectional"))
    )
    (net (code "45") (name "FRAM_MISO") (class "Default")
      (node (ref "U101") (pin "53") (pinfunction "PB14_53") (pintype "bidirectional"))
    )
    (net (code "46") (name "FRAM_MOSI") (class "Default")
      (node (ref "U101") (pin "54") (pinfunction "PB15_54") (pintype "bidirectional"))
    )
    (net (code "47") (name "FRAM_SCK") (class "Default")
      (node (ref "U101") (pin "52") (pinfunction "PB13_52") (pintype "bidirectional"))
    )
    (net (code "48") (name "GND") (class "Default")
      (node (ref "C1") (pin "2") (pinfunction "2_2") (pintype "passive"))
      (node (ref "C10") (pin "2") (pinfunction "2_2") (pintype "passive"))
      (node (ref "C1001") (pin "P$2") (pinfunction "2_P$2") (pintype "passive"))
      (node (ref "C1002") (pin "P$2") (pinfunction "2_P$2") (pintype "passive"))
      (node (ref "C1003") (pin "P$2") (pinfunction "2_P$2") (pintype "passive"))
      (node (ref "C1004") (pin "P$2") (pinfunction "2_P$2") (pintype "passive"))
      (node (ref "C102") (pin "P$2") (pinfunction "2_P$2") (pintype "passive"))
      (node (ref "C103") (pin "P$1") (pinfunction "1_P$1") (pintype "passive"))
      (node (ref "C11") (pin "P$2") (pinfunction "2_P$2") (pintype "passive"))
      (node (ref "C12") (pin "P$2") (pinfunction "2_P$2") (pintype "passive"))
      (node (ref "C13") (pin "P$2") (pinfunction "2_P$2") (pintype "passive"))
      (node (ref "C14") (pin "P$2") (pinfunction "2_P$2") (pintype "passive"))
      (node (ref "C15") (pin "P$2") (pinfunction "2_P$2") (pintype "passive"))
      (node (ref "C2") (pin "P$2") (pinfunction "2_P$2") (pintype "passive"))
      (node (ref "C3") (pin "P$2") (pinfunction "2_P$2") (pintype "passive"))
      (node (ref "C4") (pin "P$2") (pinfunction "2_P$2") (pintype "passive"))
      (node (ref "C402") (pin "P$2") (pinfunction "2_P$2") (pintype "passive"))
      (node (ref "C5") (pin "P$2") (pinfunction "2_P$2") (pintype "passive"))
      (node (ref "C505") (pin "P$2") (pinfunction "2_P$2") (pintype "passive"))
      (node (ref "C506") (pin "P$2") (pinfunction "2_P$2") (pintype "passive"))
      (node (ref "C6") (pin "P$2") (pinfunction "2_P$2") (pintype "passive"))
      (node (ref "C601") (pin "P$2") (pinfunction "2_P$2") (pintype "passive"))
      (node (ref "C602") (pin "P$1") (pinfunction "1_P$1") (pintype "passive"))
      (node (ref "C603") (pin "P$2") (pinfunction "2_P$2") (pintype "passive"))
      (node (ref "C604") (pin "P$2") (pinfunction "2_P$2") (pintype "passive"))
      (node (ref "C605") (pin "P$2") (pinfunction "2_P$2") (pintype "passive"))
      (node (ref "C606") (pin "P$2") (pinfunction "2_P$2") (pintype "passive"))
      (node (ref "C607") (pin "P$2") (pinfunction "2_P$2") (pintype "passive"))
      (node (ref "C608") (pin "P$2") (pinfunction "2_P$2") (pintype "passive"))
      (node (ref "C609") (pin "P$1") (pinfunction "1_P$1") (pintype "passive"))
      (node (ref "C610") (pin "P$2") (pinfunction "2_P$2") (pintype "passive"))
      (node (ref "C611") (pin "P$2") (pinfunction "2_P$2") (pintype "passive"))
      (node (ref "C612") (pin "P$2") (pinfunction "2_P$2") (pintype "passive"))
      (node (ref "C613") (pin "P$2") (pinfunction "2_P$2") (pintype "passive"))
      (node (ref "C7") (pin "P$2") (pinfunction "2_P$2") (pintype "passive"))
      (node (ref "C8") (pin "2") (pinfunction "2_2") (pintype "passive"))
      (node (ref "C9") (pin "2") (pinfunction "2_2") (pintype "passive"))
      (node (ref "D3") (pin "2") (pinfunction "A_2") (pintype "passive"))
      (node (ref "GND") (pin "P$1") (pinfunction "P$1_P$1") (pintype "passive"))
      (node (ref "GND.") (pin "P$1") (pinfunction "P$1_P$1") (pintype "passive"))
      (node (ref "J1") (pin "GND_S1") (pinfunction "S_GND_S1") (pintype "passive"))
      (node (ref "J1") (pin "GND_S2") (pinfunction "S_GND_S2") (pintype "passive"))
      (node (ref "J1") (pin "GND_S3") (pinfunction "S_GND_S3") (pintype "passive"))
      (node (ref "J1") (pin "GND_S4") (pinfunction "S_GND_S4") (pintype "passive"))
      (node (ref "J1") (pin "GND_S5") (pinfunction "S_GND_S5") (pintype "passive"))
      (node (ref "J1") (pin "GND_S6") (pinfunction "S_GND_S6") (pintype "passive"))
      (node (ref "J1") (pin "GND_S7") (pinfunction "S_GND_S7") (pintype "passive"))
      (node (ref "J1") (pin "GND_S8") (pinfunction "S_GND_S8") (pintype "passive"))
      (node (ref "J2") (pin "P$4") (pinfunction "4_P$4") (pintype "passive"))
      (node (ref "J201") (pin "P$6") (pinfunction "6_P$6") (pintype "passive"))
      (node (ref "J202") (pin "P$6") (pinfunction "6_P$6") (pintype "passive"))
      (node (ref "J203") (pin "P$6") (pinfunction "6_P$6") (pintype "passive"))
      (node (ref "J3") (pin "P$4") (pinfunction "4_P$4") (pintype "passive"))
      (node (ref "J302") (pin "P$4") (pinfunction "4_P$4") (pintype "passive"))
      (node (ref "J401") (pin "P$4") (pinfunction "4_P$4") (pintype "passive"))
      (node (ref "J403") (pin "P$7") (pinfunction "7_P$7") (pintype "passive"))
      (node (ref "J405") (pin "P$4") (pinfunction "4_P$4") (pintype "passive"))
      (node (ref "JP5") (pin "2") (pinfunction "2_2") (pintype "passive"))
      (node (ref "JX301") (pin "3") (pinfunction "S_3") (pintype "passive"))
      (node (ref "JX301") (pin "5") (pinfunction "S_5") (pintype "passive"))
      (node (ref "JX301") (pin "9") (pinfunction "S_9") (pintype "passive"))
      (node (ref "L1") (pin "P$EP") (pinfunction "GND_P$EP") (pintype "power_in"))
      (node (ref "L2") (pin "P$EP") (pinfunction "GND_P$EP") (pintype "power_in"))
      (node (ref "L201") (pin "P$3") (pinfunction "P$3_P$3") (pintype "bidirectional"))
      (node (ref "L201") (pin "P$4") (pinfunction "P$3_P$4") (pintype "bidirectional"))
      (node (ref "L201") (pin "P$5") (pinfunction "P$3_P$5") (pintype "bidirectional"))
      (node (ref "L202") (pin "P$3") (pinfunction "P$3_P$3") (pintype "bidirectional"))
      (node (ref "L202") (pin "P$4") (pinfunction "P$3_P$4") (pintype "bidirectional"))
      (node (ref "L202") (pin "P$5") (pinfunction "P$3_P$5") (pintype "bidirectional"))
      (node (ref "L203") (pin "P$3") (pinfunction "P$3_P$3") (pintype "bidirectional"))
      (node (ref "L203") (pin "P$4") (pinfunction "P$3_P$4") (pintype "bidirectional"))
      (node (ref "L203") (pin "P$5") (pinfunction "P$3_P$5") (pintype "bidirectional"))
      (node (ref "L3") (pin "P$EP") (pinfunction "GND_P$EP") (pintype "power_in"))
      (node (ref "L4") (pin "P$3") (pinfunction "P$3_P$3") (pintype "bidirectional"))
      (node (ref "L4") (pin "P$4") (pinfunction "P$3_P$4") (pintype "bidirectional"))
      (node (ref "L4") (pin "P$5") (pinfunction "P$3_P$5") (pintype "bidirectional"))
      (node (ref "L402") (pin "P$3") (pinfunction "P$3_P$3") (pintype "bidirectional"))
      (node (ref "L402") (pin "P$4") (pinfunction "P$3_P$4") (pintype "bidirectional"))
      (node (ref "L402") (pin "P$5") (pinfunction "P$3_P$5") (pintype "bidirectional"))
      (node (ref "L403") (pin "P$3") (pinfunction "P$3_P$3") (pintype "bidirectional"))
      (node (ref "L403") (pin "P$4") (pinfunction "P$3_P$4") (pintype "bidirectional"))
      (node (ref "L403") (pin "P$5") (pinfunction "P$3_P$5") (pintype "bidirectional"))
      (node (ref "L5") (pin "P$3") (pinfunction "P$3_P$3") (pintype "bidirectional"))
      (node (ref "L5") (pin "P$4") (pinfunction "P$3_P$4") (pintype "bidirectional"))
      (node (ref "L5") (pin "P$5") (pinfunction "P$3_P$5") (pintype "bidirectional"))
      (node (ref "L6") (pin "P$EP") (pinfunction "GND_P$EP") (pintype "power_in"))
      (node (ref "L7") (pin "P$3") (pinfunction "P$3_P$3") (pintype "bidirectional"))
      (node (ref "L7") (pin "P$4") (pinfunction "P$3_P$4") (pintype "bidirectional"))
      (node (ref "L7") (pin "P$5") (pinfunction "P$3_P$5") (pintype "bidirectional"))
      (node (ref "R1002") (pin "P$1") (pinfunction "1_P$1") (pintype "passive"))
      (node (ref "R102") (pin "P$2") (pinfunction "2_P$2") (pintype "passive"))
      (node (ref "R5") (pin "P$1") (pinfunction "1_P$1") (pintype "passive"))
      (node (ref "R603") (pin "P$1") (pinfunction "1_P$1") (pintype "passive"))
      (node (ref "R606") (pin "P$2") (pinfunction "2_P$2") (pintype "passive"))
      (node (ref "R610") (pin "P$2") (pinfunction "2_P$2") (pintype "passive"))
      (node (ref "R611") (pin "P$1") (pinfunction "1_P$1") (pintype "passive"))
      (node (ref "R711") (pin "P$1") (pinfunction "1_P$1") (pintype "passive"))
      (node (ref "R713") (pin "P$2") (pinfunction "2_P$2") (pintype "passive"))
      (node (ref "R919") (pin "P$1") (pinfunction "1_P$1") (pintype "passive"))
      (node (ref "S601") (pin "B3") (pinfunction "2_B3") (pintype "passive"))
      (node (ref "U$1") (pin "3") (pinfunction "3_3") (pintype "bidirectional"))
      (node (ref "U$1002") (pin "2") (pinfunction "GND_2") (pintype "bidirectional"))
      (node (ref "U$1002") (pin "GND") (pinfunction "GND_GND") (pintype "bidirectional"))
      (node (ref "U$14") (pin "3") (pinfunction "3_3") (pintype "bidirectional"))
      (node (ref "U$15") (pin "11") (pinfunction "GND_11") (pintype "power_in"))
      (node (ref "U$15") (pin "15") (pinfunction "PGND_15") (pintype "power_in"))
      (node (ref "U$15") (pin "16") (pinfunction "PGND_16") (pintype "power_in"))
      (node (ref "U$15") (pin "17") (pinfunction "PGND_17") (pintype "power_in"))
      (node (ref "U$15") (pin "18") (pinfunction "PGND_18") (pintype "power_in"))
      (node (ref "U$15") (pin "19") (pinfunction "PGND_19") (pintype "power_in"))
      (node (ref "U$15") (pin "20") (pinfunction "PGND_20") (pintype "power_in"))
      (node (ref "U$15") (pin "21") (pinfunction "PGND_21") (pintype "power_in"))
      (node (ref "U$15") (pin "22") (pinfunction "PGND_22") (pintype "power_in"))
      (node (ref "U$15") (pin "23") (pinfunction "PGND_23") (pintype "power_in"))
      (node (ref "U$15") (pin "4") (pinfunction "PS/SYNC_4") (pintype "input"))
      (node (ref "U$15") (pin "6") (pinfunction "PGND_6") (pintype "power_in"))
      (node (ref "U$15") (pin "7") (pinfunction "PGND_7") (pintype "power_in"))
      (node (ref "U$15") (pin "8") (pinfunction "PGND_8") (pintype "power_in"))
      (node (ref "U$15") (pin "9") (pinfunction "PGND_9") (pintype "power_in"))
      (node (ref "U$15") (pin "EP") (pinfunction "PGND_EP") (pintype "power_in"))
      (node (ref "U$2") (pin "10") (pinfunction "RSV1_10") (pintype "input"))
      (node (ref "U$2") (pin "5") (pinfunction "GND_5") (pintype "power_in"))
      (node (ref "U$201") (pin "A") (pinfunction "A_A") (pintype "passive"))
      (node (ref "U$202") (pin "A") (pinfunction "A_A") (pintype "passive"))
      (node (ref "U$203") (pin "A") (pinfunction "A_A") (pintype "passive"))
      (node (ref "U$3") (pin "4") (pinfunction "GND_4") (pintype "bidirectional"))
      (node (ref "U$4") (pin "A") (pinfunction "A_A") (pintype "passive"))
      (node (ref "U$401") (pin "A") (pinfunction "A_A") (pintype "passive"))
      (node (ref "U$402") (pin "A") (pinfunction "A_A") (pintype "passive"))
      (node (ref "U$404") (pin "A") (pinfunction "A_A") (pintype "passive"))
      (node (ref "U$5") (pin "2") (pinfunction "GND_2") (pintype "bidirectional"))
      (node (ref "U$604") (pin "2") (pinfunction "VSS_2") (pintype "bidirectional"))
      (node (ref "U$604") (pin "6") (pinfunction "VBAT_6") (pintype "bidirectional"))
      (node (ref "U$604") (pin "GND") (pinfunction "VSS_GND") (pintype "bidirectional"))
      (node (ref "U$604") (pin "P$2") (pinfunction "VSS_P$2") (pintype "bidirectional"))
      (node (ref "U$604") (pin "P$3") (pinfunction "VSS_P$3") (pintype "bidirectional"))
      (node (ref "U$605") (pin "2") (pinfunction "GND_2") (pintype "bidirectional"))
      (node (ref "U$605") (pin "GND") (pinfunction "GND_GND") (pintype "bidirectional"))
      (node (ref "U$7") (pin "A") (pinfunction "A_A") (pintype "passive"))
      (node (ref "U$701") (pin "A") (pinfunction "A_A") (pintype "passive"))
      (node (ref "U$801") (pin "A") (pinfunction "A_A") (pintype "passive"))
      (node (ref "U101") (pin "10") (pinfunction "VSS_10") (pintype "power_in"))
      (node (ref "U101") (pin "20") (pinfunction "VSSA_20") (pintype "power_in"))
      (node (ref "U101") (pin "27") (pinfunction "VSS_27") (pintype "power_in"))
      (node (ref "U101") (pin "74") (pinfunction "VSS_74") (pintype "power_in"))
      (node (ref "U101") (pin "99") (pinfunction "VSS_99") (pintype "power_in"))
      (node (ref "U2") (pin "2") (pinfunction "GND_2") (pintype "power_in"))
      (node (ref "U2") (pin "5") (pinfunction "SHDN_5") (pintype "input"))
      (node (ref "U2") (pin "8") (pinfunction "RS_8") (pintype "input"))
      (node (ref "U401") (pin "2") (pinfunction "GND_2") (pintype "power_in"))
      (node (ref "U401") (pin "5") (pinfunction "SHDN_5") (pintype "input"))
      (node (ref "U401") (pin "8") (pinfunction "RS_8") (pintype "input"))
      (node (ref "X101") (pin "2") (pinfunction "NC_2_2") (pintype "power_in"))
      (node (ref "X101") (pin "4") (pinfunction "NC_4_4") (pintype "power_in"))
    )
    (net (code "49") (name "GPIO_EXT_1") (class "Default")
      (node (ref "J403") (pin "P$6") (pinfunction "6_P$6") (pintype "passive"))
      (node (ref "U101") (pin "8") (pinfunction "PC14_8") (pintype "bidirectional"))
    )
    (net (code "50") (name "GYRO_DRDY") (class "Default")
      (node (ref "U$2") (pin "9") (pinfunction "INT2_9") (pintype "bidirectional"))
      (node (ref "U101") (pin "35") (pinfunction "PB0_35") (pintype "bidirectional"))
    )
    (net (code "51") (name "IO-~{RESET}") (class "Default")
      (node (ref "U$1002") (pin "3") (pinfunction "POR2_3") (pintype "bidirectional"))
    )
    (net (code "52") (name "MAG_DRDY") (class "Default")
      (node (ref "U101") (pin "36") (pinfunction "PB1_36") (pintype "bidirectional"))
    )
    (net (code "53") (name "Net-(C2-1)") (class "Default")
      (node (ref "C2") (pin "P$1") (pinfunction "1_P$1") (pintype "passive"))
      (node (ref "R408") (pin "P$2") (pinfunction "2_P$2") (pintype "passive"))
      (node (ref "U$1") (pin "2") (pinfunction "2_2") (pintype "bidirectional"))
    )
    (net (code "54") (name "Net-(C3-1)") (class "Default")
      (node (ref "C3") (pin "P$1") (pinfunction "1_P$1") (pintype "passive"))
      (node (ref "R407") (pin "P$2") (pinfunction "2_P$2") (pintype "passive"))
      (node (ref "U$1") (pin "1") (pinfunction "1_1") (pintype "bidirectional"))
    )
    (net (code "55") (name "Net-(C5-1)") (class "Default")
      (node (ref "C5") (pin "P$1") (pinfunction "1_P$1") (pintype "passive"))
      (node (ref "U$2") (pin "13") (pinfunction "REGD_13") (pintype "power_in"))
    )
    (net (code "56") (name "Net-(C6-1)") (class "Default")
      (node (ref "C6") (pin "P$1") (pinfunction "1_P$1") (pintype "passive"))
      (node (ref "U$15") (pin "10") (pinfunction "VAUX_10") (pintype "input"))
    )
    (net (code "57") (name "Net-(C102-1)") (class "Default")
      (node (ref "C102") (pin "P$1") (pinfunction "1_P$1") (pintype "passive"))
      (node (ref "U101") (pin "12") (pinfunction "OSC_IN_12") (pintype "input"))
      (node (ref "X101") (pin "3") (pinfunction "3_3") (pintype "bidirectional"))
    )
    (net (code "58") (name "Net-(C103-2)") (class "Default")
      (node (ref "C103") (pin "P$2") (pinfunction "2_P$2") (pintype "passive"))
      (node (ref "U101") (pin "13") (pinfunction "OSC_OUT_13") (pintype "output"))
      (node (ref "X101") (pin "1") (pinfunction "1_1") (pintype "bidirectional"))
    )
    (net (code "59") (name "Net-(C602-2)") (class "Default")
      (node (ref "C602") (pin "P$2") (pinfunction "2_P$2") (pintype "passive"))
      (node (ref "U$605") (pin "6") (pinfunction "CSET_6") (pintype "bidirectional"))
    )
    (net (code "60") (name "Net-(C611-1)") (class "Default")
      (node (ref "C611") (pin "P$1") (pinfunction "1_P$1") (pintype "passive"))
      (node (ref "U101") (pin "49") (pinfunction "VCAP_1_49") (pintype "power_in"))
    )
    (net (code "61") (name "Net-(C613-1)") (class "Default")
      (node (ref "C613") (pin "P$1") (pinfunction "1_P$1") (pintype "passive"))
      (node (ref "U101") (pin "73") (pinfunction "VCAP_2_73") (pintype "power_in"))
    )
    (net (code "62") (name "Net-(C1002-1)") (class "Default")
      (node (ref "C1002") (pin "P$1") (pinfunction "1_P$1") (pintype "passive"))
      (node (ref "U$1002") (pin "6") (pinfunction "CSET_6") (pintype "bidirectional"))
    )
    (net (code "63") (name "Net-(D3-C)") (class "Default")
      (node (ref "D3") (pin "1") (pinfunction "C_1") (pintype "passive"))
      (node (ref "R918") (pin "P$2") (pinfunction "2_P$2") (pintype "passive"))
      (node (ref "R922") (pin "P$1") (pinfunction "1_P$1") (pintype "passive"))
    )
    (net (code "64") (name "Net-(J1A-S)") (class "Default")
      (node (ref "J1") (pin "S1") (pinfunction "S_S1") (pintype "passive"))
      (node (ref "L1") (pin "P$16") (pinfunction "P$2_P$16") (pintype "bidirectional"))
    )
    (net (code "65") (name "Net-(J1B-S)") (class "Default")
      (node (ref "J1") (pin "S2") (pinfunction "S_S2") (pintype "passive"))
      (node (ref "L1") (pin "P$15") (pinfunction "P$2_P$15") (pintype "bidirectional"))
    )
    (net (code "66") (name "Net-(J1C-S)") (class "Default")
      (node (ref "J1") (pin "S3") (pinfunction "S_S3") (pintype "passive"))
      (node (ref "L1") (pin "P$14") (pinfunction "P$2_P$14") (pintype "bidirectional"))
    )
    (net (code "67") (name "Net-(J1D-S)") (class "Default")
      (node (ref "J1") (pin "S4") (pinfunction "S_S4") (pintype "passive"))
      (node (ref "L1") (pin "P$13") (pinfunction "P$2_P$13") (pintype "bidirectional"))
    )
    (net (code "68") (name "Net-(J1E-S)") (class "Default")
      (node (ref "J1") (pin "S5") (pinfunction "S_S5") (pintype "passive"))
      (node (ref "L1") (pin "P$12") (pinfunction "P$2_P$12") (pintype "bidirectional"))
    )
    (net (code "69") (name "Net-(J1F-S)") (class "Default")
      (node (ref "J1") (pin "S6") (pinfunction "S_S6") (pintype "passive"))
      (node (ref "L1") (pin "P$11") (pinfunction "P$2_P$11") (pintype "bidirectional"))
    )
    (net (code "70") (name "Net-(J1G-S)") (class "Default")
      (node (ref "J1") (pin "S7") (pinfunction "S_S7") (pintype "passive"))
      (node (ref "L1") (pin "P$10") (pinfunction "P$2_P$10") (pintype "bidirectional"))
    )
    (net (code "71") (name "Net-(J1H-S)") (class "Default")
      (node (ref "J1") (pin "S8") (pinfunction "S_S8") (pintype "passive"))
      (node (ref "L1") (pin "P$9") (pinfunction "P$2_P$9") (pintype "bidirectional"))
    )
    (net (code "72") (name "Net-(J2-1)") (class "Default")
      (node (ref "J2") (pin "P$1") (pinfunction "1_P$1") (pintype "passive"))
      (node (ref "L5") (pin "P$2") (pinfunction "P$2_P$2") (pintype "bidirectional"))
      (node (ref "U$4") (pin "C") (pinfunction "C_C") (pintype "passive"))
    )
    (net (code "73") (name "Net-(J2-2)") (class "Default")
      (node (ref "J2") (pin "P$2") (pinfunction "2_P$2") (pintype "passive"))
      (node (ref "L6") (pin "P$15") (pinfunction "P$2_P$15") (pintype "bidirectional"))
    )
    (net (code "74") (name "Net-(J2-3)") (class "Default")
      (node (ref "J2") (pin "P$3") (pinfunction "3_P$3") (pintype "passive"))
      (node (ref "L6") (pin "P$16") (pinfunction "P$2_P$16") (pintype "bidirectional"))
    )
    (net (code "75") (name "Net-(J3-1)") (class "Default")
      (node (ref "J3") (pin "P$1") (pinfunction "1_P$1") (pintype "passive"))
      (node (ref "L7") (pin "P$2") (pinfunction "P$2_P$2") (pintype "bidirectional"))
      (node (ref "U$7") (pin "C") (pinfunction "C_C") (pintype "passive"))
    )
    (net (code "76") (name "Net-(J3-2)") (class "Default")
      (node (ref "J3") (pin "P$2") (pinfunction "2_P$2") (pintype "passive"))
      (node (ref "R4") (pin "P$1") (pinfunction "1_P$1") (pintype "passive"))
      (node (ref "U2") (pin "7") (pinfunction "CANH_7") (pintype "bidirectional"))
    )
    (net (code "77") (name "Net-(J3-3)") (class "Default")
      (node (ref "J3") (pin "P$3") (pinfunction "3_P$3") (pintype "passive"))
      (node (ref "SJ2") (pin "2") (pinfunction "2_2") (pintype "passive"))
      (node (ref "U2") (pin "6") (pinfunction "CANL_6") (pintype "bidirectional"))
    )
    (net (code "78") (name "Net-(J201-1)") (class "Default")
      (node (ref "J201") (pin "P$1") (pinfunction "1_P$1") (pintype "passive"))
      (node (ref "L201") (pin "P$2") (pinfunction "P$2_P$2") (pintype "bidirectional"))
      (node (ref "U$201") (pin "C") (pinfunction "C_C") (pintype "passive"))
    )
    (net (code "79") (name "Net-(J202-1)") (class "Default")
      (node (ref "J202") (pin "P$1") (pinfunction "1_P$1") (pintype "passive"))
      (node (ref "L202") (pin "P$2") (pinfunction "P$2_P$2") (pintype "bidirectional"))
      (node (ref "U$202") (pin "C") (pinfunction "C_C") (pintype "passive"))
    )
    (net (code "80") (name "Net-(J203-1)") (class "Default")
      (node (ref "J203") (pin "P$1") (pinfunction "1_P$1") (pintype "passive"))
      (node (ref "L203") (pin "P$2") (pinfunction "P$2_P$2") (pintype "bidirectional"))
      (node (ref "U$203") (pin "C") (pinfunction "C_C") (pintype "passive"))
    )
    (net (code "81") (name "Net-(J302-2)") (class "Default")
      (node (ref "J302") (pin "P$2") (pinfunction "2_P$2") (pintype "passive"))
      (node (ref "U$5") (pin "1") (pinfunction "D1I_1") (pintype "bidirectional"))
    )
    (net (code "82") (name "Net-(J302-3)") (class "Default")
      (node (ref "J302") (pin "P$3") (pinfunction "3_P$3") (pintype "passive"))
      (node (ref "U$5") (pin "3") (pinfunction "D2I_3") (pintype "bidirectional"))
    )
    (net (code "83") (name "Net-(J401-1)") (class "Default")
      (node (ref "J401") (pin "P$1") (pinfunction "1_P$1") (pintype "passive"))
      (node (ref "L4") (pin "P$2") (pinfunction "P$2_P$2") (pintype "bidirectional"))
      (node (ref "U$401") (pin "C") (pinfunction "C_C") (pintype "passive"))
    )
    (net (code "84") (name "Net-(J401-2)") (class "Default")
      (node (ref "J401") (pin "P$2") (pinfunction "2_P$2") (pintype "passive"))
      (node (ref "L6") (pin "P$9") (pinfunction "P$2_P$9") (pintype "bidirectional"))
    )
    (net (code "85") (name "Net-(J401-3)") (class "Default")
      (node (ref "J401") (pin "P$3") (pinfunction "3_P$3") (pintype "passive"))
      (node (ref "L6") (pin "P$10") (pinfunction "P$2_P$10") (pintype "bidirectional"))
    )
    (net (code "86") (name "Net-(J403-1)") (class "Default")
      (node (ref "J403") (pin "P$1") (pinfunction "1_P$1") (pintype "passive"))
      (node (ref "L402") (pin "P$2") (pinfunction "P$2_P$2") (pintype "bidirectional"))
      (node (ref "U$402") (pin "C") (pinfunction "C_C") (pintype "passive"))
    )
    (net (code "87") (name "Net-(J405-1)") (class "Default")
      (node (ref "J405") (pin "P$1") (pinfunction "1_P$1") (pintype "passive"))
      (node (ref "L403") (pin "P$2") (pinfunction "P$2_P$2") (pintype "bidirectional"))
      (node (ref "U$404") (pin "C") (pinfunction "C_C") (pintype "passive"))
    )
    (net (code "88") (name "Net-(J802-2)") (class "Default")
      (node (ref "J802") (pin "P$2") (pinfunction "2_P$2") (pintype "passive"))
      (node (ref "R710") (pin "P$1") (pinfunction "1_P$1") (pintype "passive"))
    )
    (net (code "89") (name "Net-(L3C-P$2)") (class "Default")
      (node (ref "L3") (pin "P$13") (pinfunction "P$2_P$13") (pintype "bidirectional"))
      (node (ref "L3") (pin "P$14") (pinfunction "P$2_P$14") (pintype "bidirectional"))
      (node (ref "U$14") (pin "1") (pinfunction "1_1") (pintype "bidirectional"))
    )
    (net (code "90") (name "Net-(R3-1)") (class "Default")
      (node (ref "R3") (pin "P$1") (pinfunction "1_P$1") (pintype "passive"))
      (node (ref "R707") (pin "P$2") (pinfunction "2_P$2") (pintype "passive"))
    )
    (net (code "91") (name "Net-(R3-2)") (class "Default")
      (node (ref "LED701") (pin "C") (pinfunction "C_C") (pintype "passive"))
      (node (ref "R3") (pin "P$2") (pinfunction "2_P$2") (pintype "passive"))
    )
    (net (code "92") (name "Net-(R4-2)") (class "Default")
      (node (ref "R4") (pin "P$2") (pinfunction "2_P$2") (pintype "passive"))
      (node (ref "SJ2") (pin "1") (pinfunction "1_1") (pintype "passive"))
    )
    (net (code "93") (name "Net-(R102-1)") (class "Default")
      (node (ref "R102") (pin "P$1") (pinfunction "1_P$1") (pintype "passive"))
      (node (ref "U101") (pin "37") (pinfunction "PB2_37") (pintype "bidirectional"))
    )
    (net (code "94") (name "Net-(R409-2)") (class "Default")
      (node (ref "R409") (pin "P$2") (pinfunction "2_P$2") (pintype "passive"))
      (node (ref "SJ1") (pin "1") (pinfunction "1_1") (pintype "passive"))
    )
    (net (code "95") (name "Net-(R606-1)") (class "Default")
      (node (ref "R606") (pin "P$1") (pinfunction "1_P$1") (pintype "passive"))
      (node (ref "U$604") (pin "7") (pinfunction "ILIM_7") (pintype "bidirectional"))
    )
    (net (code "96") (name "Net-(R711-2)") (class "Default")
      (node (ref "LED704") (pin "C") (pinfunction "C_C") (pintype "passive"))
      (node (ref "R711") (pin "P$2") (pinfunction "2_P$2") (pintype "passive"))
    )
    (net (code "97") (name "Net-(R712-2)") (class "Default")
      (node (ref "LED705") (pin "C") (pinfunction "C_C") (pintype "passive"))
      (node (ref "R712") (pin "P$2") (pinfunction "2_P$2") (pintype "passive"))
    )
    (net (code "98") (name "Net-(U$15-L1)") (class "Default")
      (node (ref "U$15") (pin "1") (pinfunction "L1_1") (pintype "bidirectional"))
      (node (ref "U$16") (pin "2") (pinfunction "2_2") (pintype "passive"))
    )
    (net (code "99") (name "Net-(U$15-L2)") (class "Default")
      (node (ref "U$15") (pin "14") (pinfunction "L2_14") (pintype "bidirectional"))
      (node (ref "U$16") (pin "1") (pinfunction "1_1") (pintype "passive"))
    )
    (net (code "100") (name "OTG_FS_DM") (class "Default")
      (node (ref "U$5") (pin "4") (pinfunction "D2O_4") (pintype "bidirectional"))
      (node (ref "U101") (pin "70") (pinfunction "PA11_70") (pintype "bidirectional"))
    )
    (net (code "101") (name "OTG_FS_DP") (class "Default")
      (node (ref "U$5") (pin "6") (pinfunction "D1O_6") (pintype "bidirectional"))
      (node (ref "U101") (pin "71") (pinfunction "PA12_71") (pintype "bidirectional"))
    )
    (net (code "102") (name "PPM_INPUT") (class "Default")
      (node (ref "L3") (pin "P$3") (pinfunction "P$1_P$3") (pintype "bidirectional"))
      (node (ref "U101") (pin "23") (pinfunction "PA0_23") (pintype "bidirectional"))
    )
    (net (code "103") (name "SAFETY") (class "Default")
      (node (ref "J802") (pin "P$3") (pinfunction "3_P$3") (pintype "passive"))
      (node (ref "R713") (pin "P$1") (pinfunction "1_P$1") (pintype "passive"))
    )
    (net (code "104") (name "SDIO_CK") (class "Default")
      (node (ref "U$3") (pin "6") (pinfunction "CLK_6") (pintype "bidirectional"))
      (node (ref "U101") (pin "80") (pinfunction "PC12_80") (pintype "bidirectional"))
    )
    (net (code "105") (name "SDIO_CMD") (class "Default")
      (node (ref "U$3") (pin "1") (pinfunction "~{CS}_1") (pintype "bidirectional"))
      (node (ref "U101") (pin "83") (pinfunction "PD2_83") (pintype "bidirectional"))
    )
    (net (code "106") (name "SDIO_D0") (class "Default")
      (node (ref "U$3") (pin "5") (pinfunction "DI/IO0_5") (pintype "bidirectional"))
      (node (ref "U101") (pin "65") (pinfunction "PC8_65") (pintype "bidirectional"))
    )
    (net (code "107") (name "SDIO_D1") (class "Default")
      (node (ref "U$3") (pin "2") (pinfunction "DO/IO1_2") (pintype "bidirectional"))
      (node (ref "U101") (pin "66") (pinfunction "PC9_66") (pintype "bidirectional"))
    )
    (net (code "108") (name "SDIO_D2") (class "Default")
      (node (ref "U$3") (pin "3") (pinfunction "~{WP}/IO2_3") (pintype "bidirectional"))
      (node (ref "U101") (pin "78") (pinfunction "PC10_78") (pintype "bidirectional"))
    )
    (net (code "109") (name "SDIO_D3") (class "Default")
      (node (ref "U$3") (pin "7") (pinfunction "~{HOLD}/IO3_7") (pintype "bidirectional"))
      (node (ref "U101") (pin "79") (pinfunction "PC11_79") (pintype "bidirectional"))
    )
    (net (code "110") (name "SERIAL1_CTS") (class "Default")
      (node (ref "J201") (pin "P$4") (pinfunction "4_P$4") (pintype "passive"))
      (node (ref "L2") (pin "P$9") (pinfunction "P$2_P$9") (pintype "bidirectional"))
    )
    (net (code "111") (name "SERIAL1_RTS") (class "Default")
      (node (ref "J201") (pin "P$5") (pinfunction "5_P$5") (pintype "passive"))
      (node (ref "L2") (pin "P$10") (pinfunction "P$2_P$10") (pintype "bidirectional"))
    )
    (net (code "112") (name "SERIAL1_RX") (class "Default")
      (node (ref "J201") (pin "P$3") (pinfunction "3_P$3") (pintype "passive"))
      (node (ref "L2") (pin "P$12") (pinfunction "P$2_P$12") (pintype "bidirectional"))
      (node (ref "S1RX") (pin "P$1") (pinfunction "P$1_P$1") (pintype "passive"))
    )
    (net (code "113") (name "SERIAL1_TX") (class "Default")
      (node (ref "J201") (pin "P$2") (pinfunction "2_P$2") (pintype "passive"))
      (node (ref "L2") (pin "P$11") (pinfunction "P$2_P$11") (pintype "bidirectional"))
      (node (ref "S1TX") (pin "P$1") (pinfunction "P$1_P$1") (pintype "passive"))
    )
    (net (code "114") (name "SERIAL2_CTS") (class "Default")
      (node (ref "J202") (pin "P$4") (pinfunction "4_P$4") (pintype "passive"))
      (node (ref "L2") (pin "P$15") (pinfunction "P$2_P$15") (pintype "bidirectional"))
    )
    (net (code "115") (name "SERIAL2_RTS") (class "Default")
      (node (ref "J202") (pin "P$5") (pinfunction "5_P$5") (pintype "passive"))
      (node (ref "L2") (pin "P$16") (pinfunction "P$2_P$16") (pintype "bidirectional"))
    )
    (net (code "116") (name "SERIAL2_RX") (class "Default")
      (node (ref "J202") (pin "P$3") (pinfunction "3_P$3") (pintype "passive"))
      (node (ref "L2") (pin "P$14") (pinfunction "P$2_P$14") (pintype "bidirectional"))
      (node (ref "S2RX") (pin "P$1") (pinfunction "P$1_P$1") (pintype "passive"))
    )
    (net (code "117") (name "SERIAL2_TX") (class "Default")
      (node (ref "J202") (pin "P$2") (pinfunction "2_P$2") (pintype "passive"))
      (node (ref "L2") (pin "P$13") (pinfunction "P$2_P$13") (pintype "bidirectional"))
      (node (ref "S2TX") (pin "P$1") (pinfunction "P$1_P$1") (pintype "passive"))
    )
    (net (code "118") (name "SERIAL3_RX") (class "Default")
      (node (ref "J203") (pin "P$3") (pinfunction "3_P$3") (pintype "passive"))
      (node (ref "L3") (pin "P$12") (pinfunction "P$2_P$12") (pintype "bidirectional"))
      (node (ref "S3RX") (pin "P$1") (pinfunction "P$1_P$1") (pintype "passive"))
    )
    (net (code "119") (name "SERIAL3_TX") (class "Default")
      (node (ref "J203") (pin "P$2") (pinfunction "2_P$2") (pintype "passive"))
      (node (ref "L3") (pin "P$11") (pinfunction "P$2_P$11") (pintype "bidirectional"))
      (node (ref "S3TX") (pin "P$1") (pinfunction "P$1_P$1") (pintype "passive"))
    )
    (net (code "120") (name "SPEKTRUM_RX") (class "Default")
      (node (ref "L3") (pin "P$4") (pinfunction "P$1_P$4") (pintype "bidirectional"))
      (node (ref "U101") (pin "69") (pinfunction "PA10_69") (pintype "bidirectional"))
    )
    (net (code "121") (name "SPI_EXT_MISO") (class "Default")
      (node (ref "J403") (pin "P$3") (pinfunction "3_P$3") (pintype "passive"))
      (node (ref "U101") (pin "4") (pinfunction "PE5_4") (pintype "bidirectional"))
    )
    (net (code "122") (name "SPI_EXT_MOSI") (class "Default")
      (node (ref "J403") (pin "P$4") (pinfunction "4_P$4") (pintype "passive"))
      (node (ref "U101") (pin "5") (pinfunction "PE6_5") (pintype "bidirectional"))
    )
    (net (code "123") (name "SPI_EXT_SCK") (class "Default")
      (node (ref "J403") (pin "P$2") (pinfunction "2_P$2") (pintype "passive"))
      (node (ref "U101") (pin "1") (pinfunction "PE2_1") (pintype "bidirectional"))
    )
    (net (code "124") (name "SPI_INT_MISO") (class "Default")
      (node (ref "U$2") (pin "7") (pinfunction "SA0/MISO_7") (pintype "bidirectional"))
      (node (ref "U101") (pin "31") (pinfunction "PA6_31") (pintype "bidirectional"))
    )
    (net (code "125") (name "SPI_INT_MOSI") (class "Default")
      (node (ref "U$2") (pin "6") (pinfunction "SDA/MOSI_6") (pintype "bidirectional"))
      (node (ref "U101") (pin "32") (pinfunction "PA7_32") (pintype "bidirectional"))
    )
    (net (code "126") (name "SPI_INT_SCK") (class "Default")
      (node (ref "U$2") (pin "4") (pinfunction "SCL/CLK_4") (pintype "bidirectional"))
      (node (ref "U101") (pin "30") (pinfunction "PA5_30") (pintype "bidirectional"))
    )
    (net (code "127") (name "VBAT") (class "Default")
      (node (ref "R608") (pin "P$1") (pinfunction "1_P$1") (pintype "passive"))
      (node (ref "U101") (pin "6") (pinfunction "VBAT_6") (pintype "power_in"))
    )
    (net (code "128") (name "VBUS") (class "Default")
      (node (ref "D1") (pin "ANODE") (pinfunction "A_ANODE") (pintype "passive"))
      (node (ref "J302") (pin "P$1") (pinfunction "1_P$1") (pintype "passive"))
      (node (ref "U$5") (pin "5") (pinfunction "VBUS_5") (pintype "bidirectional"))
      (node (ref "U101") (pin "68") (pinfunction "PA9_68") (pintype "bidirectional"))
    )
    (net (code "129") (name "VDD_3V3_PERIPH") (class "Default")
      (node (ref "C1004") (pin "P$1") (pinfunction "1_P$1") (pintype "passive"))
      (node (ref "U$1002") (pin "7") (pinfunction "VOUT2_7") (pintype "bidirectional"))
    )
    (net (code "130") (name "VDD_3V3_PERIPH_EN") (class "Default")
      (node (ref "R5") (pin "P$2") (pinfunction "2_P$2") (pintype "passive"))
      (node (ref "U$1002") (pin "4") (pinfunction "EN2_4") (pintype "bidirectional"))
    )
    (net (code "131") (name "VDD_3V3_SENSORS") (class "Default")
      (node (ref "C1003") (pin "P$1") (pinfunction "1_P$1") (pintype "passive"))
      (node (ref "C505") (pin "P$1") (pinfunction "1_P$1") (pintype "passive"))
      (node (ref "C506") (pin "P$1") (pinfunction "1_P$1") (pintype "passive"))
      (node (ref "U$1002") (pin "8") (pinfunction "VOUT1_8") (pintype "bidirectional"))
      (node (ref "U$2") (pin "1") (pinfunction "VDD_IO_1") (pintype "power_in"))
      (node (ref "U$2") (pin "14") (pinfunction "VDD_14") (pintype "power_in"))
      (node (ref "U$2") (pin "15") (pinfunction "RSV2_15") (pintype "input"))
      (node (ref "VDDA_3V3_SENSORS") (pin "P$1") (pinfunction "P$1_P$1") (pintype "passive"))
    )
    (net (code "132") (name "VDD_3V3_SENSORS_EN") (class "Default")
      (node (ref "R1002") (pin "P$2") (pinfunction "2_P$2") (pintype "passive"))
      (node (ref "U$1002") (pin "5") (pinfunction "EN1_5") (pintype "bidirectional"))
      (node (ref "U101") (pin "2") (pinfunction "PE3_2") (pintype "bidirectional"))
    )
    (net (code "133") (name "VDD_3V3_SPEKTRUM") (class "Default")
      (node (ref "C605") (pin "P$1") (pinfunction "1_P$1") (pintype "passive"))
      (node (ref "U$14") (pin "2") (pinfunction "2_2") (pintype "bidirectional"))
      (node (ref "U$605") (pin "8") (pinfunction "VOUT1_8") (pintype "bidirectional"))
      (node (ref "U$801") (pin "C") (pinfunction "C_C") (pintype "passive"))
    )
    (net (code "134") (name "VDD_3V3_SPEKTRUM_EN") (class "Default")
      (node (ref "R603") (pin "P$2") (pinfunction "2_P$2") (pintype "passive"))
      (node (ref "U$605") (pin "5") (pinfunction "EN1_5") (pintype "bidirectional"))
    )
    (net (code "135") (name "VDD_5V") (class "Default")
      (node (ref "C10") (pin "1") (pinfunction "1_1") (pintype "passive"))
      (node (ref "C1001") (pin "P$1") (pinfunction "1_P$1") (pintype "passive"))
      (node (ref "C11") (pin "P$1") (pinfunction "1_P$1") (pintype "passive"))
      (node (ref "C601") (pin "P$1") (pinfunction "1_P$1") (pintype "passive"))
      (node (ref "C7") (pin "P$1") (pinfunction "1_P$1") (pintype "passive"))
      (node (ref "C8") (pin "1") (pinfunction "1_1") (pintype "passive"))
      (node (ref "C9") (pin "1") (pinfunction "1_1") (pintype "passive"))
      (node (ref "LED701") (pin "A") (pinfunction "A_A") (pintype "passive"))
      (node (ref "LED704") (pin "A") (pinfunction "A_A") (pintype "passive"))
      (node (ref "LED705") (pin "A") (pinfunction "A_A") (pintype "passive"))
      (node (ref "R6") (pin "P$2") (pinfunction "2_P$2") (pintype "passive"))
      (node (ref "R607") (pin "P$1") (pinfunction "1_P$1") (pintype "passive"))
      (node (ref "R609") (pin "P$2") (pinfunction "2_P$2") (pintype "passive"))
      (node (ref "U$1002") (pin "1") (pinfunction "VIN_1") (pintype "bidirectional"))
      (node (ref "U$15") (pin "13") (pinfunction "VOUT_13") (pintype "power_in"))
      (node (ref "U$604") (pin "1") (pinfunction "IN_1") (pintype "bidirectional"))
      (node (ref "U$605") (pin "1") (pinfunction "VIN_1") (pintype "bidirectional"))
      (node (ref "U$605") (pin "4") (pinfunction "EN2_4") (pintype "bidirectional"))
    )
    (net (code "136") (name "VDD_5V_PERIPH") (class "Default")
      (node (ref "L201") (pin "P$1") (pinfunction "P$1_P$1") (pintype "bidirectional"))
      (node (ref "L202") (pin "P$1") (pinfunction "P$1_P$1") (pintype "bidirectional"))
      (node (ref "L203") (pin "P$1") (pinfunction "P$1_P$1") (pintype "bidirectional"))
      (node (ref "L4") (pin "P$1") (pinfunction "P$1_P$1") (pintype "bidirectional"))
      (node (ref "L402") (pin "P$1") (pinfunction "P$1_P$1") (pintype "bidirectional"))
      (node (ref "L403") (pin "P$1") (pinfunction "P$1_P$1") (pintype "bidirectional"))
      (node (ref "L5") (pin "P$1") (pinfunction "P$1_P$1") (pintype "bidirectional"))
      (node (ref "L7") (pin "P$1") (pinfunction "P$1_P$1") (pintype "bidirectional"))
      (node (ref "U$604") (pin "8") (pinfunction "OUT_8") (pintype "bidirectional"))
    )
    (net (code "137") (name "VDD_5V_SENS") (class "Default")
      (node (ref "R609") (pin "P$1") (pinfunction "1_P$1") (pintype "passive"))
      (node (ref "R610") (pin "P$1") (pinfunction "1_P$1") (pintype "passive"))
      (node (ref "U101") (pin "29") (pinfunction "PA4_29") (pintype "bidirectional"))
    )
    (net (code "138") (name "VDD_IN") (class "Default")
      (node (ref "C1") (pin "1") (pinfunction "1_1") (pintype "passive"))
      (node (ref "C12") (pin "P$1") (pinfunction "1_P$1") (pintype "passive"))
      (node (ref "D1") (pin "CATHODE") (pinfunction "C_CATHODE") (pintype "passive"))
      (node (ref "D2") (pin "C") (pinfunction "C_C") (pintype "passive"))
      (node (ref "D5") (pin "C") (pinfunction "C_C") (pintype "passive"))
      (node (ref "U$15") (pin "2") (pinfunction "VIN_2") (pintype "power_in"))
      (node (ref "U$15") (pin "3") (pinfunction "EN_3") (pintype "input"))
    )
    (net (code "139") (name "VDD_SERVO_SENS") (class "Default")
      (node (ref "R918") (pin "P$1") (pinfunction "1_P$1") (pintype "passive"))
      (node (ref "R919") (pin "P$2") (pinfunction "2_P$2") (pintype "passive"))
    )
    (net (code "140") (name "V_EXT") (class "Default")
      (node (ref "D5") (pin "A") (pinfunction "A_A") (pintype "passive"))
      (node (ref "JP5") (pin "1") (pinfunction "1_1") (pintype "passive"))
    )
    (net (code "141") (name "V_SERVO") (class "Default")
      (node (ref "D2") (pin "A") (pinfunction "A_A") (pintype "passive"))
      (node (ref "J1") (pin "PWR_S1") (pinfunction "S_PWR_S1") (pintype "passive"))
      (node (ref "J1") (pin "PWR_S2") (pinfunction "S_PWR_S2") (pintype "passive"))
      (node (ref "J1") (pin "PWR_S3") (pinfunction "S_PWR_S3") (pintype "passive"))
      (node (ref "J1") (pin "PWR_S4") (pinfunction "S_PWR_S4") (pintype "passive"))
      (node (ref "J1") (pin "PWR_S5") (pinfunction "S_PWR_S5") (pintype "passive"))
      (node (ref "J1") (pin "PWR_S6") (pinfunction "S_PWR_S6") (pintype "passive"))
      (node (ref "J1") (pin "PWR_S7") (pinfunction "S_PWR_S7") (pintype "passive"))
      (node (ref "J1") (pin "PWR_S8") (pinfunction "S_PWR_S8") (pintype "passive"))
      (node (ref "R922") (pin "P$2") (pinfunction "2_P$2") (pintype "passive"))
    )
    (net (code "142") (name "unconnected-(J203-4-PadP$4)") (class "Default")
      (node (ref "J203") (pin "P$4") (pinfunction "4_P$4") (pintype "passive"))
    )
    (net (code "143") (name "unconnected-(J203-5-PadP$5)") (class "Default")
      (node (ref "J203") (pin "P$5") (pinfunction "5_P$5") (pintype "passive"))
    )
    (net (code "144") (name "unconnected-(JX301A-S-Pad10)") (class "Default")
      (node (ref "JX301") (pin "10") (pinfunction "S_10") (pintype "passive"))
    )
    (net (code "145") (name "unconnected-(JX301F-S-Pad8)") (class "Default")
      (node (ref "JX301") (pin "8") (pinfunction "S_8") (pintype "passive"))
    )
    (net (code "146") (name "unconnected-(L3-PadP$1)") (class "Default")
      (node (ref "L3") (pin "P$1") (pinfunction "P$1_P$1") (pintype "bidirectional"))
    )
    (net (code "147") (name "unconnected-(L3A-P$2-PadP$16)") (class "Default")
      (node (ref "L3") (pin "P$16") (pinfunction "P$2_P$16") (pintype "bidirectional"))
    )
    (net (code "148") (name "unconnected-(L3B-P$1-PadP$2)") (class "Default")
      (node (ref "L3") (pin "P$2") (pinfunction "P$1_P$2") (pintype "bidirectional"))
    )
    (net (code "149") (name "unconnected-(L3B-P$2-PadP$15)") (class "Default")
      (node (ref "L3") (pin "P$15") (pinfunction "P$2_P$15") (pintype "bidirectional"))
    )
    (net (code "150") (name "unconnected-(L3G-P$1-PadP$7)") (class "Default")
      (node (ref "L3") (pin "P$7") (pinfunction "P$1_P$7") (pintype "bidirectional"))
    )
    (net (code "151") (name "unconnected-(L3G-P$2-PadP$10)") (class "Default")
      (node (ref "L3") (pin "P$10") (pinfunction "P$2_P$10") (pintype "bidirectional"))
    )
    (net (code "152") (name "unconnected-(L3H-P$1-PadP$8)") (class "Default")
      (node (ref "L3") (pin "P$8") (pinfunction "P$1_P$8") (pintype "bidirectional"))
    )
    (net (code "153") (name "unconnected-(L3H-P$2-PadP$9)") (class "Default")
      (node (ref "L3") (pin "P$9") (pinfunction "P$2_P$9") (pintype "bidirectional"))
    )
    (net (code "154") (name "unconnected-(L6C-P$1-PadP$3)") (class "Default")
      (node (ref "L6") (pin "P$3") (pinfunction "P$1_P$3") (pintype "bidirectional"))
    )
    (net (code "155") (name "unconnected-(L6C-P$2-PadP$14)") (class "Default")
      (node (ref "L6") (pin "P$14") (pinfunction "P$2_P$14") (pintype "bidirectional"))
    )
    (net (code "156") (name "unconnected-(L6D-P$1-PadP$4)") (class "Default")
      (node (ref "L6") (pin "P$4") (pinfunction "P$1_P$4") (pintype "bidirectional"))
    )
    (net (code "157") (name "unconnected-(L6D-P$2-PadP$13)") (class "Default")
      (node (ref "L6") (pin "P$13") (pinfunction "P$2_P$13") (pintype "bidirectional"))
    )
    (net (code "158") (name "unconnected-(L6E-P$1-PadP$5)") (class "Default")
      (node (ref "L6") (pin "P$5") (pinfunction "P$1_P$5") (pintype "bidirectional"))
    )
    (net (code "159") (name "unconnected-(L6E-P$2-PadP$12)") (class "Default")
      (node (ref "L6") (pin "P$12") (pinfunction "P$2_P$12") (pintype "bidirectional"))
    )
    (net (code "160") (name "unconnected-(L6F-P$1-PadP$6)") (class "Default")
      (node (ref "L6") (pin "P$6") (pinfunction "P$1_P$6") (pintype "bidirectional"))
    )
    (net (code "161") (name "unconnected-(L6F-P$2-PadP$11)") (class "Default")
      (node (ref "L6") (pin "P$11") (pinfunction "P$2_P$11") (pintype "bidirectional"))
    )
    (net (code "162") (name "unconnected-(U$2-DSYNC-Pad12)") (class "Default")
      (node (ref "U$2") (pin "12") (pinfunction "DSYNC_12") (pintype "bidirectional"))
    )
    (net (code "163") (name "unconnected-(U$2-MST_SCL-Pad2)") (class "Default")
      (node (ref "U$2") (pin "2") (pinfunction "MST_SCL_2") (pintype "bidirectional"))
    )
    (net (code "164") (name "unconnected-(U$2-MST_SDA-Pad3)") (class "Default")
      (node (ref "U$2") (pin "3") (pinfunction "MST_SDA_3") (pintype "bidirectional"))
    )
    (net (code "165") (name "unconnected-(U$2-RSV3-Pad16)") (class "Default")
      (node (ref "U$2") (pin "16") (pinfunction "RSV3_16") (pintype "no_connect"))
    )
    (net (code "166") (name "unconnected-(U$15-FB-Pad12)") (class "Default")
      (node (ref "U$15") (pin "12") (pinfunction "FB_12") (pintype "input"))
    )
    (net (code "167") (name "unconnected-(U101I-PC0-Pad15)") (class "Default")
      (node (ref "U101") (pin "15") (pinfunction "PC0_15") (pintype "bidirectional"))
    )
    (net (code "168") (name "unconnected-(U101I-PC1-Pad16)") (class "Default")
      (node (ref "U101") (pin "16") (pinfunction "PC1_16") (pintype "bidirectional"))
    )
    (net (code "169") (name "unconnected-(U101I-PC2-Pad17)") (class "Default")
      (node (ref "U101") (pin "17") (pinfunction "PC2_17") (pintype "bidirectional"))
    )
    (net (code "170") (name "unconnected-(U101I-PC5-Pad34)") (class "Default")
      (node (ref "U101") (pin "34") (pinfunction "PC5_34") (pintype "bidirectional"))
    )
    (net (code "171") (name "unconnected-(U101I-PC6-Pad63)") (class "Default")
      (node (ref "U101") (pin "63") (pinfunction "PC6_63") (pintype "bidirectional"))
    )
    (net (code "172") (name "unconnected-(U101I-PC7-Pad64)") (class "Default")
      (node (ref "U101") (pin "64") (pinfunction "PC7_64") (pintype "bidirectional"))
    )
    (net (code "173") (name "unconnected-(U101L-PE10-Pad41)") (class "Default")
      (node (ref "U101") (pin "41") (pinfunction "PE10_41") (pintype "bidirectional"))
    )
    (net (code "174") (name "~{ACCEL_MAG_CS}") (class "Default")
      (node (ref "U101") (pin "9") (pinfunction "PC15_9") (pintype "bidirectional"))
    )
    (net (code "175") (name "~{BARO_CS}") (class "Default")
      (node (ref "U101") (pin "88") (pinfunction "PD7_88") (pintype "bidirectional"))
    )
    (net (code "176") (name "~{FMU-LED_AMBER}") (class "Default")
      (node (ref "R707") (pin "P$1") (pinfunction "1_P$1") (pintype "passive"))
      (node (ref "U101") (pin "43") (pinfunction "PE12_43") (pintype "bidirectional"))
    )
    (net (code "177") (name "~{FRAM_CS}") (class "Default")
      (node (ref "U101") (pin "57") (pinfunction "PD10_57") (pintype "bidirectional"))
    )
    (net (code "178") (name "~{GYRO_CS}") (class "Default")
      (node (ref "U$2") (pin "8") (pinfunction "CS_8") (pintype "bidirectional"))
      (node (ref "U101") (pin "7") (pinfunction "PC13_7") (pintype "bidirectional"))
    )
    (net (code "179") (name "~{SPI_EXT_NSS}") (class "Default")
      (node (ref "J403") (pin "P$5") (pinfunction "5_P$5") (pintype "passive"))
      (node (ref "U101") (pin "3") (pinfunction "PE4_3") (pintype "bidirectional"))
    )
    (net (code "180") (name "~{VDD_5V_PERIPH_EN}") (class "Default")
      (node (ref "R607") (pin "P$2") (pinfunction "2_P$2") (pintype "passive"))
      (node (ref "U$604") (pin "5") (pinfunction "~{CE}_5") (pintype "bidirectional"))
      (node (ref "U101") (pin "67") (pinfunction "PA8_67") (pintype "bidirectional"))
    )
    (net (code "181") (name "~{VDD_5V_PERIPH_OC}") (class "Default")
      (node (ref "U$604") (pin "4") (pinfunction "~{FAULT}_4") (pintype "bidirectional"))
      (node (ref "U101") (pin "46") (pinfunction "PE15_46") (pintype "bidirectional"))
    )
    (net (code "182") (name "~{VDD_5V_VALID}") (class "Default")
      (node (ref "R6") (pin "P$1") (pinfunction "1_P$1") (pintype "passive"))
      (node (ref "U$15") (pin "5") (pinfunction "PG_5") (pintype "output"))
      (node (ref "U101") (pin "91") (pinfunction "PB5_91") (pintype "bidirectional"))
    )
    (net (code "183") (name "~{VDD_SERVO_VALID}") (class "Default")
      (node (ref "U101") (pin "93") (pinfunction "PB7_93") (pintype "bidirectional"))
    )
  )
)
